# 94330_LM_IO_V1_2.net
KiCad netlist of a schematic drawn in Altium Designer
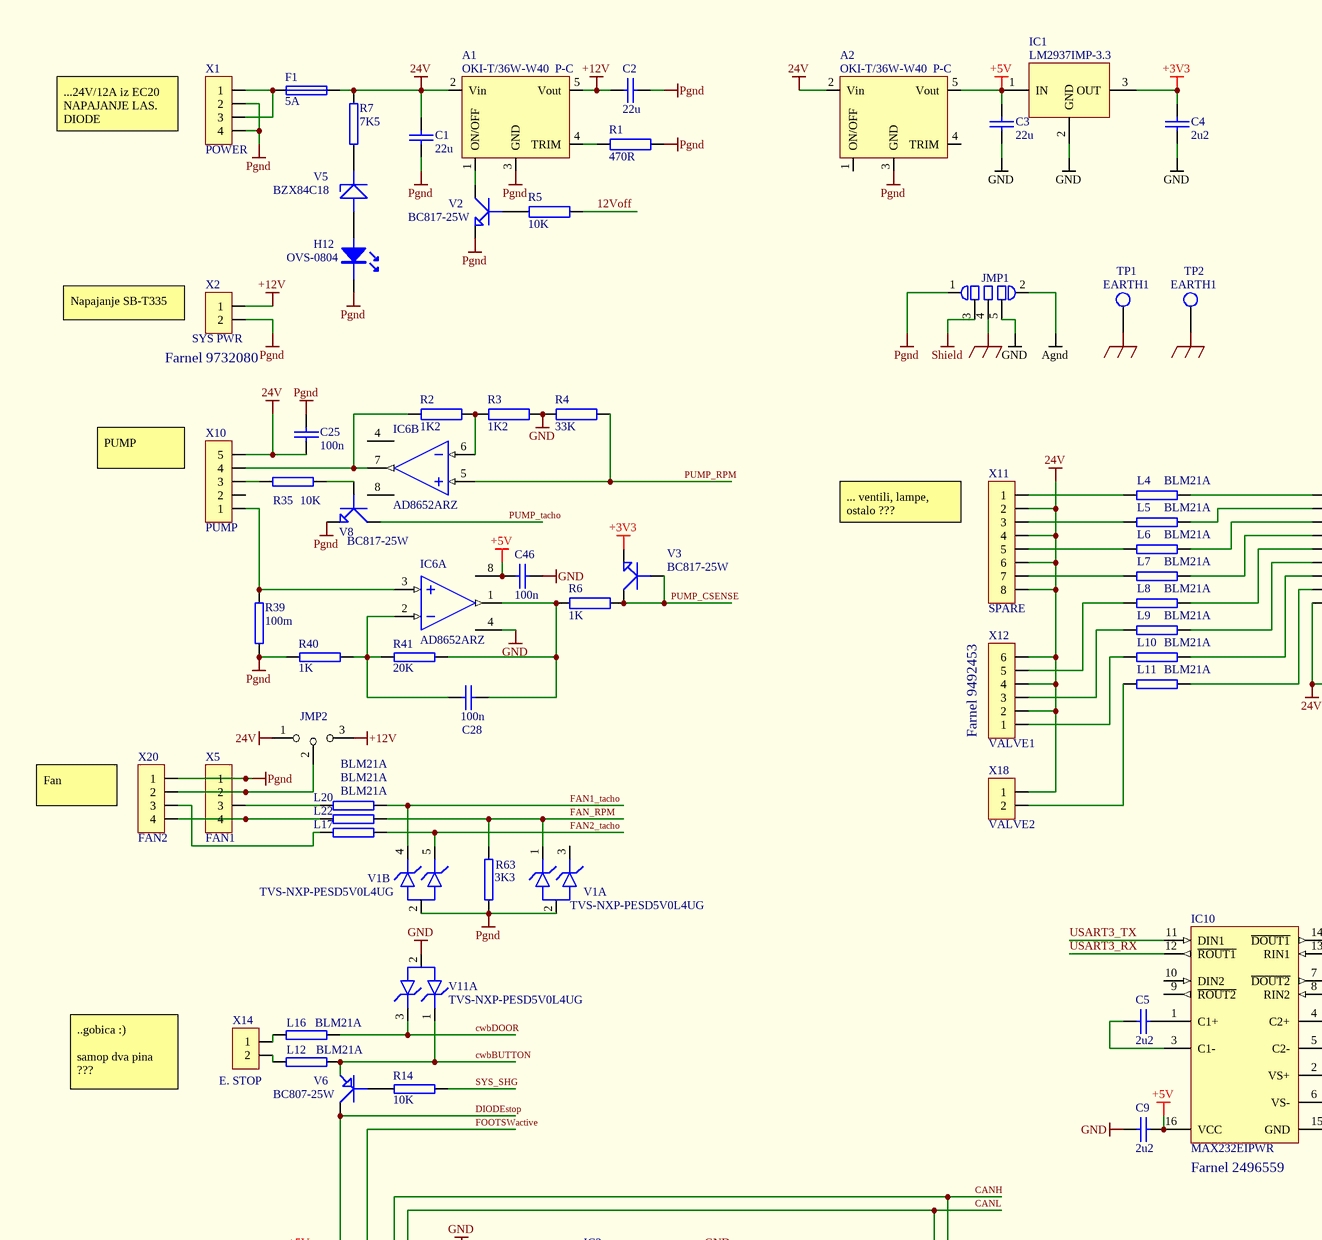
[diagram p0: 94330_LM_IO_V1.2.SchDoc, top left]
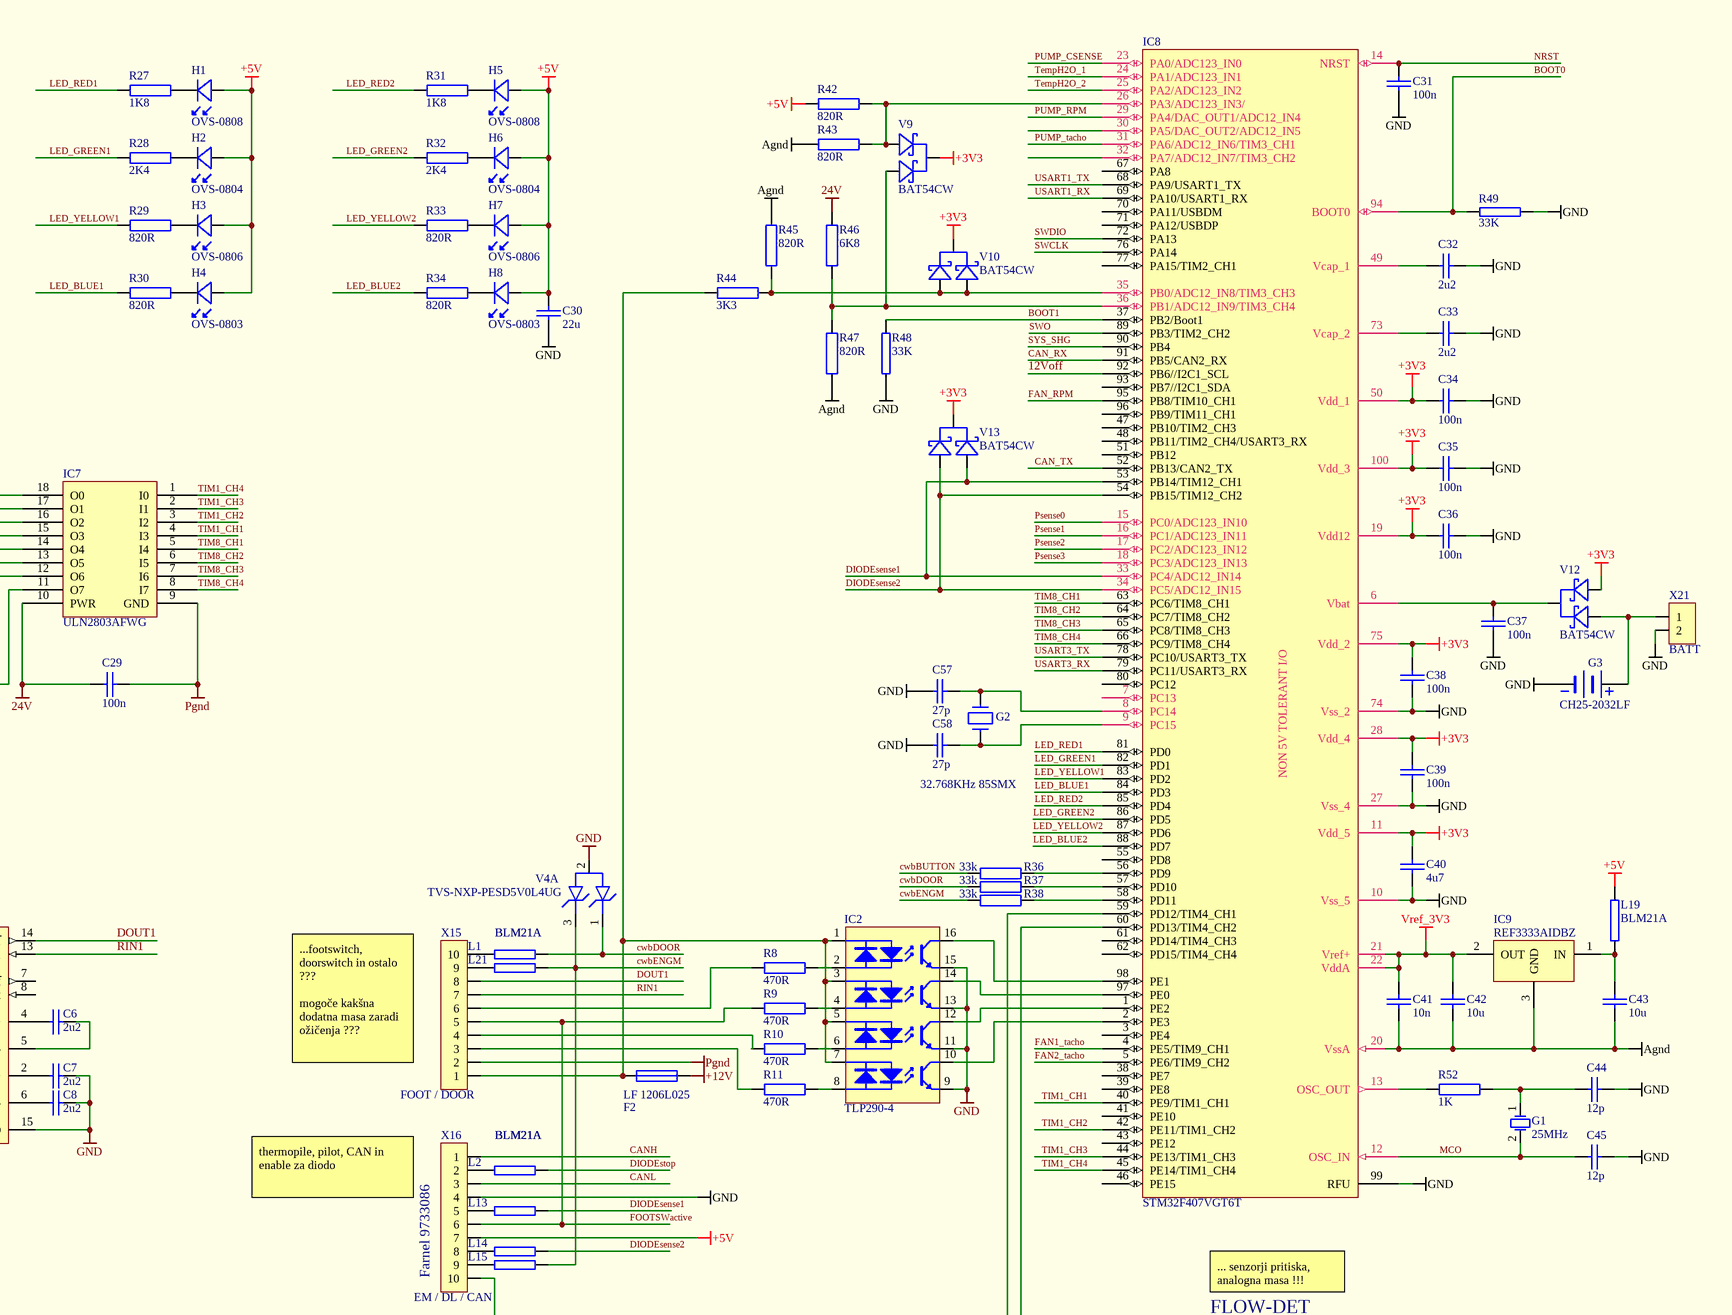
[diagram p1: 94330_LM_IO_V1.2.SchDoc, top right]
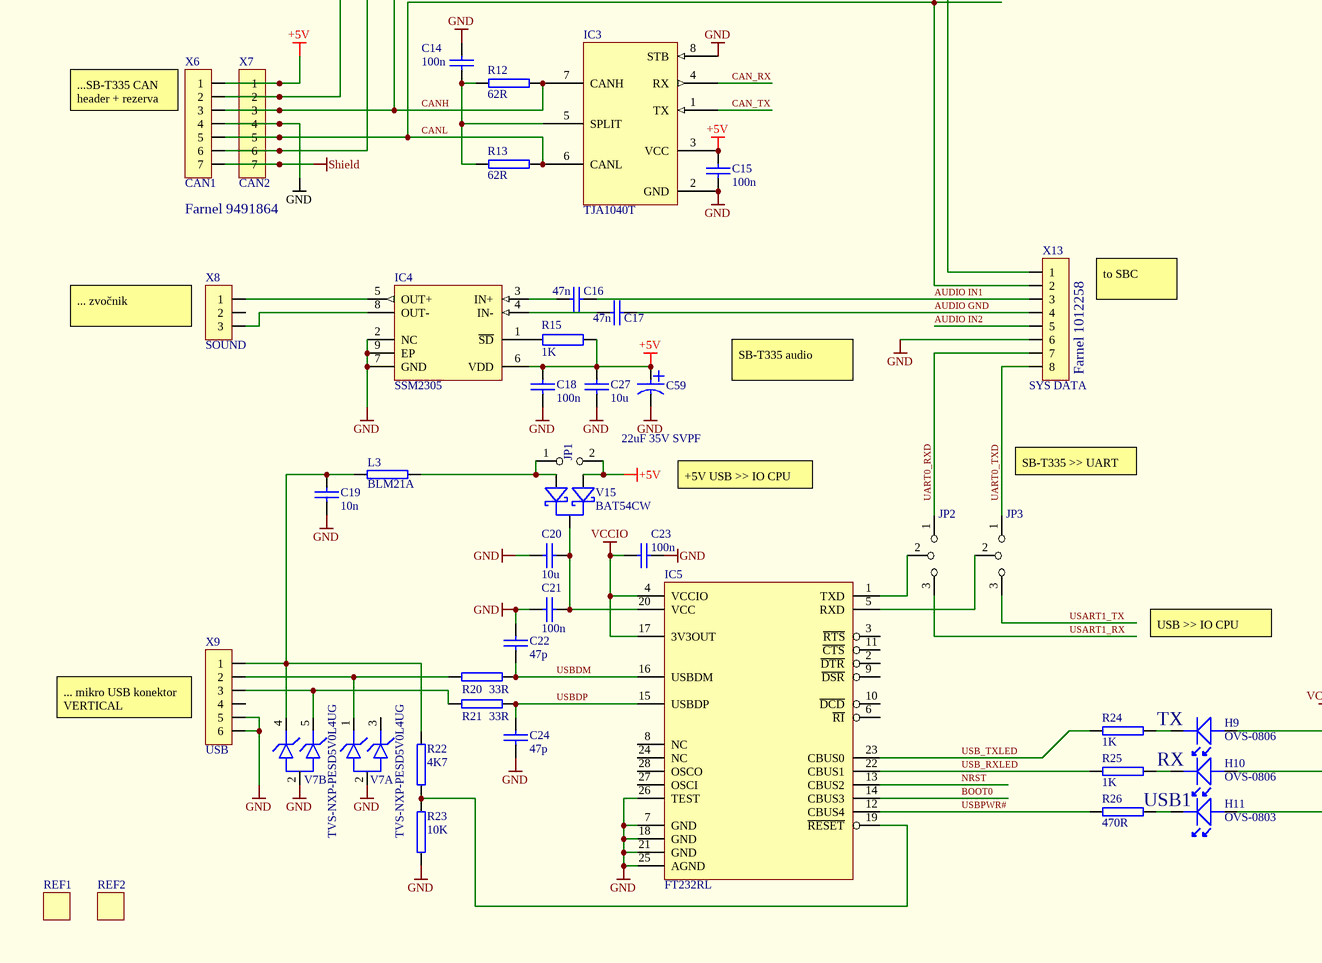
[diagram p2: 94330_LM_IO_V1.2.SchDoc, bottom left]
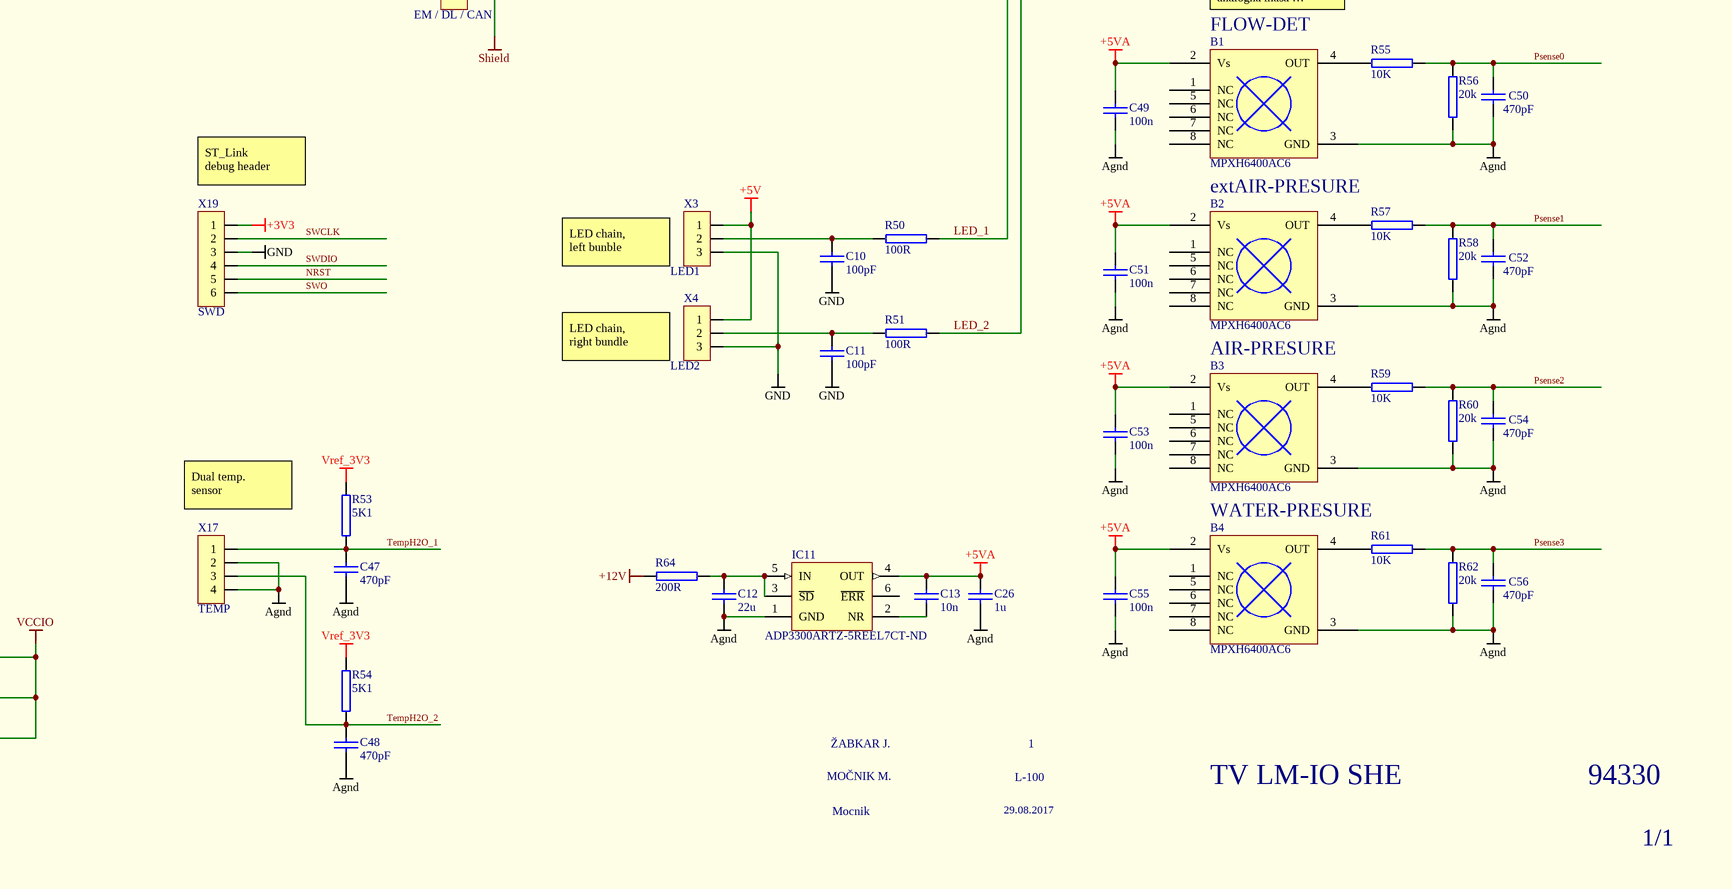
[diagram p3: 94330_LM_IO_V1.2.SchDoc, bottom right]

(export (version "E")
  (design (tool "Eeschema 10.0.6"))
  (components
    (comp (ref "A1")
      (value "OKI-T/36W-W40  P-C")
      (footprint "DC-DC_OKI-T/36W-W40")
      (libsource (lib "Mlk-sch") (part "MURATA_OKI-T/36W-W40  X-C"))
    )
    (comp (ref "A2")
      (value "OKI-T/36W-W40  P-C")
      (footprint "DC-DC_OKI-T/36W-W40")
      (libsource (lib "Mlk-sch") (part "MURATA_OKI-T/36W-W40  X-C"))
    )
    (comp (ref "B1")
      (value "MPXH6400AC6")
      (footprint "SOIC127P1030-8N_MPXH6400AC6")
      (description "MPXH6400A Pressure sensor, 400kPa")
      (libsource (lib "*") (part "MPXH6400A"))
    )
    (comp (ref "B2")
      (value "MPXH6400AC6")
      (footprint "SOIC127P1030-8N_MPXH6400AC6")
      (description "MPXH6400A Pressure sensor, 400kPa")
      (libsource (lib "*") (part "MPXH6400A"))
    )
    (comp (ref "B3")
      (value "MPXH6400AC6")
      (footprint "SOIC127P1030-8N_MPXH6400AC6")
      (description "MPXH6400A Pressure sensor, 400kPa")
      (libsource (lib "*") (part "MPXH6400A"))
    )
    (comp (ref "B4")
      (value "MPXH6400AC6")
      (footprint "SOIC127P1030-8N_MPXH6400AC6")
      (description "MPXH6400A Pressure sensor, 400kPa")
      (libsource (lib "*") (part "MPXH6400A"))
    )
    (comp (ref "C1")
      (value "22u")
      (footprint "CAPC3225N")
      (description "Capacitor 1206")
      (libsource (lib "altium-import") (part "root_2_Cap_"))
    )
    (comp (ref "C2")
      (value "22u")
      (footprint "CAPC3225N")
      (description "Capacitor 0805")
      (libsource (lib "altium-import") (part "root_1_Cap_"))
    )
    (comp (ref "C3")
      (value "22u")
      (footprint "CAPC3225N")
      (description "Capacitor 0805")
      (libsource (lib "altium-import") (part "root_0_Cap_"))
    )
    (comp (ref "C4")
      (value "2u2")
      (footprint "0805-C-IPC-V")
      (description "Capacitor 0805")
      (libsource (lib "altium-import") (part "root_0_Cap_"))
    )
    (comp (ref "C5")
      (value "2u2")
      (footprint "0805-C-IPC-V")
      (description "Capacitor 0805")
      (libsource (lib "altium-import") (part "root_1_Cap_"))
    )
    (comp (ref "C6")
      (value "2u2")
      (footprint "0805-C-IPC-V")
      (description "Capacitor 0805")
      (libsource (lib "altium-import") (part "root_1_Cap_"))
    )
    (comp (ref "C7")
      (value "2u2")
      (footprint "0805-C-IPC-V")
      (description "Capacitor 0805")
      (libsource (lib "altium-import") (part "root_1_Cap_"))
    )
    (comp (ref "C8")
      (value "2u2")
      (footprint "0805-C-IPC-V")
      (description "Capacitor 0805")
      (libsource (lib "altium-import") (part "root_1_Cap_"))
    )
    (comp (ref "C9")
      (value "2u2")
      (footprint "0805-C-IPC-V")
      (description "Capacitor 0805")
      (libsource (lib "altium-import") (part "root_3_Cap_"))
    )
    (comp (ref "C10")
      (value "100pF")
      (footprint "0805-C-IPC-V")
      (description "Capacitor 0805")
      (libsource (lib "*") (part "C"))
    )
    (comp (ref "C11")
      (value "100pF")
      (footprint "0805-C-IPC-V")
      (description "Capacitor 0805")
      (libsource (lib "*") (part "C"))
    )
    (comp (ref "C12")
      (value "22u")
      (footprint "CAPC3225N")
      (description "Capacitor 1206")
      (libsource (lib "altium-import") (part "root_2_Cap_"))
    )
    (comp (ref "C13")
      (value "10n")
      (footprint "0805-C-IPC-V")
      (description "Capacitor 0805")
      (libsource (lib "Main") (part "C"))
    )
    (comp (ref "C14")
      (value "100n")
      (footprint "0805-C-IPC-V")
      (description "Capacitor 0805")
      (libsource (lib "Main") (part "C"))
    )
    (comp (ref "C15")
      (value "100n")
      (footprint "0805-C-IPC-V")
      (description "Capacitor 0805")
      (libsource (lib "Main") (part "C"))
    )
    (comp (ref "C16")
      (value "47n")
      (footprint "0805-C-IPC-V")
      (description "Capacitor 0805")
      (libsource (lib "Main") (part "C"))
    )
    (comp (ref "C17")
      (value "47n")
      (footprint "0805-C-IPC-V")
      (description "Capacitor 0805")
      (libsource (lib "Main") (part "C"))
    )
    (comp (ref "C18")
      (value "100n")
      (footprint "0805-C-IPC-V")
      (description "Capacitor 0805")
      (libsource (lib "Main") (part "C"))
    )
    (comp (ref "C19")
      (value "10n")
      (footprint "0805-C-IPC-V")
      (description "Capacitor 0805")
      (libsource (lib "*") (part "C"))
    )
    (comp (ref "C20")
      (value "10u")
      (footprint "0805-C-IPC-V")
      (description "Capacitor 0805")
      (libsource (lib "*") (part "CAP"))
    )
    (comp (ref "C21")
      (value "100n")
      (footprint "0805-C-IPC-V")
      (description "Capacitor 0805")
      (libsource (lib "*") (part "C"))
    )
    (comp (ref "C22")
      (value "47p")
      (footprint "0805-C-V")
      (description "Capacitor 0805")
      (libsource (lib "*") (part "C"))
    )
    (comp (ref "C23")
      (value "100n")
      (footprint "0805-C-IPC-V")
      (description "Capacitor 0805")
      (libsource (lib "*") (part "C"))
    )
    (comp (ref "C24")
      (value "47p")
      (footprint "0805-C-V")
      (description "Capacitor 0805")
      (libsource (lib "*") (part "C"))
    )
    (comp (ref "C25")
      (value "100n")
      (footprint "0805-C-IPC-V")
      (description "Capacitor 0805")
      (libsource (lib "*") (part "C"))
    )
    (comp (ref "C26")
      (value "1u")
      (footprint "0805-C-IPC-V")
      (description "Capacitor 0805")
      (libsource (lib "Main") (part "C"))
    )
    (comp (ref "C27")
      (value "10u")
      (footprint "0805-C-IPC-V")
      (description "Capacitor 0805")
      (libsource (lib "altium-import") (part "root_2_Cap_"))
    )
    (comp (ref "C28")
      (value "100n")
      (footprint "0805-C-IPC-V")
      (description "Capacitor 0805")
      (libsource (lib "Fotona") (part "Cap"))
    )
    (comp (ref "C29")
      (value "100n")
      (footprint "0805-C-IPC-V")
      (description "Capacitor 0805")
      (libsource (lib "Main") (part "C"))
    )
    (comp (ref "C30")
      (value "22u")
      (footprint "0805-C-IPC-V")
      (description "Capacitor 0805")
      (libsource (lib "Fotona") (part "Cap"))
    )
    (comp (ref "C31")
      (value "100n")
      (footprint "0805-C-IPC-V")
      (description "Capacitor 0805")
      (libsource (lib "Fotona") (part "Cap"))
    )
    (comp (ref "C32")
      (value "2u2")
      (footprint "0805-C-IPC-V")
      (description "Capacitor 0805")
      (libsource (lib "Fotona") (part "Cap"))
    )
    (comp (ref "C33")
      (value "2u2")
      (footprint "0805-C-IPC-V")
      (description "Capacitor 0805")
      (libsource (lib "Fotona") (part "Cap"))
    )
    (comp (ref "C34")
      (value "100n")
      (footprint "0805-C-IPC-V")
      (description "Capacitor 0805")
      (libsource (lib "Main") (part "C"))
    )
    (comp (ref "C35")
      (value "100n")
      (footprint "0805-C-IPC-V")
      (description "Capacitor 0805")
      (libsource (lib "Main") (part "C"))
    )
    (comp (ref "C36")
      (value "100n")
      (footprint "0805-C-IPC-V")
      (description "Capacitor 0805")
      (libsource (lib "Main") (part "C"))
    )
    (comp (ref "C37")
      (value "100n")
      (footprint "0805-C-IPC-V")
      (description "Capacitor 0805")
      (libsource (lib "Main") (part "C"))
    )
    (comp (ref "C38")
      (value "100n")
      (footprint "0805-C-IPC-V")
      (description "Capacitor 0805")
      (libsource (lib "Main") (part "C"))
    )
    (comp (ref "C39")
      (value "100n")
      (footprint "0805-C-IPC-V")
      (description "Capacitor 0805")
      (libsource (lib "Main") (part "C"))
    )
    (comp (ref "C40")
      (value "4u7")
      (footprint "0805-C-IPC-V")
      (description "Capacitor 0805")
      (libsource (lib "Fotona") (part "Cap"))
    )
    (comp (ref "C41")
      (value "10n")
      (footprint "0805-C-IPC-V")
      (description "Capacitor 0805")
      (libsource (lib "Fotona") (part "Cap"))
    )
    (comp (ref "C42")
      (value "10u")
      (footprint "0805-C-IPC-V")
      (description "Capacitor 0805")
      (libsource (lib "Fotona") (part "Cap"))
    )
    (comp (ref "C43")
      (value "10u")
      (footprint "0805-C-IPC-V")
      (description "Capacitor 0805")
      (libsource (lib "Fotona") (part "Cap"))
    )
    (comp (ref "C44")
      (value "12p")
      (footprint "0805-C-IPC-V")
      (description "Capacitor 0603")
      (libsource (lib "Fotona") (part "Cap"))
    )
    (comp (ref "C45")
      (value "12p")
      (footprint "0805-C-IPC-V")
      (description "Capacitor 0603")
      (libsource (lib "Fotona") (part "Cap"))
    )
    (comp (ref "C46")
      (value "100n")
      (footprint "0805-C-IPC-V")
      (description "Capacitor 0805")
      (libsource (lib "Fotona") (part "Cap"))
    )
    (comp (ref "C47")
      (value "470pF")
      (footprint "0805-C-IPC-V")
      (description "Capacitor 0805")
      (libsource (lib "*") (part "C"))
    )
    (comp (ref "C48")
      (value "470pF")
      (footprint "0805-C-IPC-V")
      (description "Capacitor 0805")
      (libsource (lib "*") (part "C"))
    )
    (comp (ref "C49")
      (value "100n")
      (footprint "0805-C-IPC-V")
      (description "Capacitor 0805")
      (libsource (lib "Main") (part "C"))
    )
    (comp (ref "C50")
      (value "470pF")
      (footprint "0805-C-IPC-V")
      (description "Capacitor 0805")
      (libsource (lib "*") (part "C"))
    )
    (comp (ref "C51")
      (value "100n")
      (footprint "0805-C-IPC-V")
      (description "Capacitor 0805")
      (libsource (lib "Main") (part "C"))
    )
    (comp (ref "C52")
      (value "470pF")
      (footprint "0805-C-IPC-V")
      (description "Capacitor 0805")
      (libsource (lib "*") (part "C"))
    )
    (comp (ref "C53")
      (value "100n")
      (footprint "0805-C-IPC-V")
      (description "Capacitor 0805")
      (libsource (lib "Main") (part "C"))
    )
    (comp (ref "C54")
      (value "470pF")
      (footprint "0805-C-IPC-V")
      (description "Capacitor 0805")
      (libsource (lib "*") (part "C"))
    )
    (comp (ref "C55")
      (value "100n")
      (footprint "0805-C-IPC-V")
      (description "Capacitor 0805")
      (libsource (lib "Main") (part "C"))
    )
    (comp (ref "C56")
      (value "470pF")
      (footprint "0805-C-IPC-V")
      (description "Capacitor 0805")
      (libsource (lib "*") (part "C"))
    )
    (comp (ref "C57")
      (value "27p")
      (footprint "0805-C-IPC-V")
      (description "Capacitor 0603")
      (libsource (lib "Fotona") (part "Cap"))
    )
    (comp (ref "C58")
      (value "27p")
      (footprint "0805-C-IPC-V")
      (description "Capacitor 0603")
      (libsource (lib "Fotona") (part "Cap"))
    )
    (comp (ref "C59")
      (value "22uF 35V SVPF")
      (footprint "CAPAE66W54HN")
      (libsource (lib "Mlk-sch") (part "C-EL"))
    )
    (comp (ref "F1")
      (value "5A")
      (footprint "FUSE_154_ LITTELFUSE")
      (description "FUSE")
      (libsource (lib "MA_DEVICE_1") (part "FUSE"))
    )
    (comp (ref "F2") (value "LF 1206L025") (footprint "FUSEC3216X09N") (libsource (lib "*") (part "FUSE1")))
    (comp (ref "G1")
      (value "25MHz")
      (footprint "JXG53P2")
      (description "SMD Quartz Crystal")
      (libsource (lib "Fotona") (part "XTAL"))
    )
    (comp (ref "G2")
      (value "32.768KHz 85SMX")
      (footprint "QUARTZ-85SMX")
      (libsource (lib "*") (part "CRYSTAL"))
    )
    (comp (ref "G3")
      (value "CH25-2032LF")
      (footprint "BATTERY HOLDER-20")
      (description "Li CELL 3V, 3/2 PIN, HOR/VERT POS")
      (libsource (lib "Mlk-sch") (part "BATTERY LI 3V"))
    )
    (comp (ref "H1")
      (value "OVS-0808")
      (footprint "LED_0805_RED")
      (description "LED")
      (libsource (lib "Fotona") (part "LED"))
    )
    (comp (ref "H2")
      (value "OVS-0804")
      (footprint "LED_0805_GREEN")
      (description "LED")
      (libsource (lib "Fotona") (part "LED"))
    )
    (comp (ref "H3")
      (value "OVS-0806")
      (footprint "LED_0805_YELLOW")
      (description "LED")
      (libsource (lib "Fotona") (part "LED"))
    )
    (comp (ref "H4")
      (value "OVS-0803")
      (footprint "LED_0805_BLUE")
      (description "LED")
      (libsource (lib "Fotona") (part "LED"))
    )
    (comp (ref "H5")
      (value "OVS-0808")
      (footprint "LED_0805_RED")
      (description "LED")
      (libsource (lib "Fotona") (part "LED"))
    )
    (comp (ref "H6")
      (value "OVS-0804")
      (footprint "LED_0805_GREEN")
      (description "LED")
      (libsource (lib "Fotona") (part "LED"))
    )
    (comp (ref "H7")
      (value "OVS-0806")
      (footprint "LED_0805_YELLOW")
      (description "LED")
      (libsource (lib "Fotona") (part "LED"))
    )
    (comp (ref "H8")
      (value "OVS-0803")
      (footprint "LED_0805_BLUE")
      (description "LED")
      (libsource (lib "Fotona") (part "LED"))
    )
    (comp (ref "H9")
      (value "OVS-0806")
      (footprint "LED_0805_YELLOW")
      (description "LED")
      (libsource (lib "*") (part "LED0805"))
    )
    (comp (ref "H10")
      (value "OVS-0806")
      (footprint "LED_0805_YELLOW")
      (description "LED")
      (libsource (lib "*") (part "LED0805"))
    )
    (comp (ref "H11")
      (value "OVS-0803")
      (footprint "LED_0805_BLUE")
      (description "LED")
      (libsource (lib "*") (part "LED0805"))
    )
    (comp (ref "H12")
      (value "OVS-0804")
      (footprint "LED_0805_GREEN")
      (description "LED")
      (libsource (lib "MA_DEVICE_1") (part "D_LED"))
    )
    (comp (ref "IC1")
      (value "LM2937IMP-3.3")
      (footprint "FOTONA_IPC7351_DISCRETE:SOT223-4N-V")
      (description "Fixed 3V3 Regulator")
      (libsource (lib "Fotona") (part "LM2937IMP"))
    )
    (comp (ref "IC2")
      (value "TLP290-4")
      (footprint "SOIC127P700X265-16N")
      (libsource (lib "Mlk-sch") (part "OPTOCOUPLER-QUAD"))
    )
    (comp (ref "IC3") (value "TJA1040T") (footprint "SO_8") (libsource (lib "*") (part "TJA1040")))
    (comp (ref "IC4")
      (value "SSM2305")
      (footprint "SON50P300X85_HS-9N")
      (libsource (lib "Mlk-sch") (part "SSM2305"))
    )
    (comp (ref "IC5")
      (value "FT232RL")
      (footprint "SOP65P780-28N")
      (description "USB to Serial port converter")
      (libsource (lib "*") (part "FT232RL"))
    )
    (comp (ref "IC6")
      (value "AD8652ARZ")
      (footprint "SOIC127P600-8N")
      (description "Dual CMOS RR Op Amp")
      (libsource (lib "Fotona") (part "OPAMP_DUAL"))
    )
    (comp (ref "IC7")
      (value "ULN2803AFWG")
      (footprint "SOIC127P1030-18N")
      (description "COIL DRIVER")
      (libsource (lib "*") (part "ULN2804"))
    )
    (comp (ref "IC8")
      (value "STM32F407VGT6T")
      (footprint "LQFP100_N")
      (description "STM32 ARM-based 32-bit MCU with 1024 Kbytes Flash, 100-pin LQFP")
      (libsource (lib "Fotona") (part "STM32F205VGT6"))
    )
    (comp (ref "IC9")
      (value "REF3333AIDBZ")
      (footprint "FOTONA_IPC7351_DISCRETE:SOT23-3N")
      (description "3V3 Voltage Reference")
      (libsource (lib "Fotona") (part "REF33XX"))
    )
    (comp (ref "IC10")
      (value "MAX232EIPWR")
      (footprint "FOTONA_IPC7351_SO:TSOP65P640-16N")
      (libsource (lib "altium-import") (part "root_0_CMP-0299-00572-2_"))
    )
    (comp (ref "IC11")
      (value "ADP3300ARTZ-5REEL7CT-ND")
      (footprint "SOT23-6N")
      (libsource (lib "Mlk-sch") (part "ADP3300"))
    )
    (comp (ref "JMP1") (value "~") (libsource (lib "*") (part "JUMPER SMD5X")))
    (comp (ref "JMP2") (value "~") (description "JUMPER") (libsource (lib "MA_DEVICE_1") (part "JMP3")))
    (comp (ref "JP1")
      (value "JMP2")
      (footprint "SIP_2")
      (description "JUMPER")
      (libsource (lib "MA_DEVICE_1") (part "JMP2"))
    )
    (comp (ref "JP2")
      (value "~")
      (footprint "SIP_3")
      (description "JUMPER")
      (libsource (lib "MA_DEVICE_1") (part "JMP3"))
    )
    (comp (ref "JP3")
      (value "~")
      (footprint "SIP_3")
      (description "JUMPER")
      (libsource (lib "MA_DEVICE_1") (part "JMP3"))
    )
    (comp (ref "L1")
      (value "BLM21A")
      (footprint "INDC2012N")
      (description "Ferite Bead SMT")
      (libsource (lib "*") (part "BLM21"))
    )
    (comp (ref "L2")
      (value "BLM21A")
      (footprint "INDC2012N")
      (description "Ferite Bead SMT")
      (libsource (lib "*") (part "BLM21"))
    )
    (comp (ref "L3")
      (value "BLM21A")
      (footprint "INDC2012N")
      (description "Ferite Bead SMT")
      (libsource (lib "*") (part "BLM21"))
    )
    (comp (ref "L4")
      (value "BLM21A")
      (footprint "INDC2012N")
      (description "FERITE MURATA BLM21")
      (libsource (lib "*") (part "BLM21"))
    )
    (comp (ref "L5")
      (value "BLM21A")
      (footprint "INDC2012N")
      (description "FERITE MURATA BLM21")
      (libsource (lib "*") (part "BLM21"))
    )
    (comp (ref "L6")
      (value "BLM21A")
      (footprint "INDC2012N")
      (description "FERITE MURATA BLM21")
      (libsource (lib "*") (part "BLM21"))
    )
    (comp (ref "L7")
      (value "BLM21A")
      (footprint "INDC2012N")
      (description "FERITE MURATA BLM21")
      (libsource (lib "*") (part "BLM21"))
    )
    (comp (ref "L8")
      (value "BLM21A")
      (footprint "INDC2012N")
      (description "FERITE MURATA BLM21")
      (libsource (lib "*") (part "BLM21"))
    )
    (comp (ref "L9")
      (value "BLM21A")
      (footprint "INDC2012N")
      (description "FERITE MURATA BLM21")
      (libsource (lib "*") (part "BLM21"))
    )
    (comp (ref "L10")
      (value "BLM21A")
      (footprint "INDC2012N")
      (description "FERITE MURATA BLM21")
      (libsource (lib "*") (part "BLM21"))
    )
    (comp (ref "L11")
      (value "BLM21A")
      (footprint "INDC2012N")
      (description "FERITE MURATA BLM21")
      (libsource (lib "*") (part "BLM21"))
    )
    (comp (ref "L12")
      (value "BLM21A")
      (footprint "INDC2012N")
      (description "Ferite Bead SMT")
      (libsource (lib "*") (part "BLM21"))
    )
    (comp (ref "L13")
      (value "BLM21A")
      (footprint "INDC2012N")
      (description "Ferite Bead SMT")
      (libsource (lib "*") (part "BLM21"))
    )
    (comp (ref "L14")
      (value "BLM21A")
      (footprint "INDC2012N")
      (description "Ferite Bead SMT")
      (libsource (lib "*") (part "BLM21"))
    )
    (comp (ref "L15")
      (value "BLM21A")
      (footprint "INDC2012N")
      (description "Ferite Bead SMT")
      (libsource (lib "*") (part "BLM21"))
    )
    (comp (ref "L16")
      (value "BLM21A")
      (footprint "INDC2012N")
      (description "Ferite Bead SMT")
      (libsource (lib "*") (part "BLM21"))
    )
    (comp (ref "L17")
      (value "BLM21A")
      (footprint "INDC2012N")
      (description "FERITE MURATA BLM21")
      (libsource (lib "*") (part "BLM21"))
    )
    (comp (ref "L19")
      (value "BLM21A")
      (footprint "INDC2012N")
      (description "Ferite Bead SMT")
      (libsource (lib "*") (part "BLM21"))
    )
    (comp (ref "L20")
      (value "BLM21A")
      (footprint "INDC2012N")
      (description "FERITE MURATA BLM21")
      (libsource (lib "*") (part "BLM21"))
    )
    (comp (ref "L21")
      (value "BLM21A")
      (footprint "INDC2012N")
      (description "Ferite Bead SMT")
      (libsource (lib "*") (part "BLM21"))
    )
    (comp (ref "L22")
      (value "BLM21A")
      (footprint "INDC2012N")
      (description "FERITE MURATA BLM21")
      (libsource (lib "*") (part "BLM21"))
    )
    (comp (ref "R1")
      (value "470R")
      (footprint "0805-R-IPC-V")
      (description "Chip Resistor 0805")
      (libsource (lib "Fotona") (part "Res"))
    )
    (comp (ref "R2")
      (value "1K2")
      (footprint "0805-R-IPC-V")
      (description "Chip Resistor 0805")
      (libsource (lib "Fotona") (part "Res"))
    )
    (comp (ref "R3")
      (value "1K2")
      (footprint "0805-R-IPC-V")
      (description "Chip Resistor 0805")
      (libsource (lib "Fotona") (part "Res"))
    )
    (comp (ref "R4")
      (value "33K")
      (footprint "0805-R-V")
      (description "Chip Resistor 0805")
      (libsource (lib "Fotona") (part "Res"))
    )
    (comp (ref "R5")
      (value "10K")
      (footprint "0805-R-IPC-V")
      (description "Chip Resistor 0805")
      (libsource (lib "Fotona") (part "Res"))
    )
    (comp (ref "R6")
      (value "1K")
      (footprint "0805-R-IPC-V")
      (description "Chip Resistor 0805")
      (libsource (lib "Fotona") (part "Res"))
    )
    (comp (ref "R7")
      (value "7K5")
      (footprint "0805-R-IPC-V")
      (description "Resistor")
      (libsource (lib "*") (part "R"))
    )
    (comp (ref "R8")
      (value "470R")
      (footprint "0805-R-IPC-V")
      (description "Chip Resistor 0805")
      (libsource (lib "Fotona") (part "Res"))
    )
    (comp (ref "R9")
      (value "470R")
      (footprint "0805-R-IPC-V")
      (description "Chip Resistor 0805")
      (libsource (lib "Fotona") (part "Res"))
    )
    (comp (ref "R10")
      (value "470R")
      (footprint "0805-R-IPC-V")
      (description "Chip Resistor 0805")
      (libsource (lib "Fotona") (part "Res"))
    )
    (comp (ref "R11")
      (value "470R")
      (footprint "0805-R-IPC-V")
      (description "Chip Resistor 0805")
      (libsource (lib "Fotona") (part "Res"))
    )
    (comp (ref "R12")
      (value "62R")
      (footprint "0805-R-IPC-V")
      (description "Resistor")
      (libsource (lib "Main") (part "R"))
    )
    (comp (ref "R13")
      (value "62R")
      (footprint "0805-R-IPC-V")
      (description "Resistor")
      (libsource (lib "Main") (part "R"))
    )
    (comp (ref "R14")
      (value "10K")
      (footprint "0805-R-IPC-V")
      (description "Resistor")
      (libsource (lib "Main") (part "R"))
    )
    (comp (ref "R15")
      (value "1K")
      (footprint "0805-R-IPC-V")
      (description "Chip Resistor 0805")
      (libsource (lib "Fotona") (part "Res"))
    )
    (comp (ref "R20")
      (value "33R")
      (footprint "0805-R-IPC-V")
      (description "Resistor")
      (libsource (lib "*") (part "R"))
    )
    (comp (ref "R21")
      (value "33R")
      (footprint "0805-R-IPC-V")
      (description "Resistor")
      (libsource (lib "*") (part "R"))
    )
    (comp (ref "R22")
      (value "4K7")
      (footprint "0805-R-IPC-V")
      (description "Resistor")
      (libsource (lib "*") (part "R"))
    )
    (comp (ref "R23")
      (value "10K")
      (footprint "0805-R-IPC-V")
      (description "Resistor")
      (libsource (lib "*") (part "R"))
    )
    (comp (ref "R24")
      (value "1K")
      (footprint "0805-R-IPC-V")
      (description "Resistor")
      (libsource (lib "*") (part "R"))
    )
    (comp (ref "R25")
      (value "1K")
      (footprint "0805-R-IPC-V")
      (description "Resistor")
      (libsource (lib "*") (part "R"))
    )
    (comp (ref "R26")
      (value "470R")
      (footprint "0805-R-IPC-V")
      (description "Resistor")
      (libsource (lib "*") (part "R"))
    )
    (comp (ref "R27")
      (value "1K8")
      (footprint "0805-R-IPC-V")
      (description "Chip Resistor 0805")
      (libsource (lib "Fotona") (part "Res"))
    )
    (comp (ref "R28")
      (value "2K4")
      (footprint "0805-R-IPC-V")
      (description "Chip Resistor 0805")
      (libsource (lib "Fotona") (part "Res"))
    )
    (comp (ref "R29")
      (value "820R")
      (footprint "0805-R-IPC-V")
      (description "Chip Resistor 0805")
      (libsource (lib "Fotona") (part "Res"))
    )
    (comp (ref "R30")
      (value "820R")
      (footprint "0805-R-IPC-V")
      (description "Chip Resistor 0805")
      (libsource (lib "Fotona") (part "Res"))
    )
    (comp (ref "R31")
      (value "1K8")
      (footprint "0805-R-IPC-V")
      (description "Chip Resistor 0805")
      (libsource (lib "Fotona") (part "Res"))
    )
    (comp (ref "R32")
      (value "2K4")
      (footprint "0805-R-IPC-V")
      (description "Chip Resistor 0805")
      (libsource (lib "Fotona") (part "Res"))
    )
    (comp (ref "R33")
      (value "820R")
      (footprint "0805-R-IPC-V")
      (description "Chip Resistor 0805")
      (libsource (lib "Fotona") (part "Res"))
    )
    (comp (ref "R34")
      (value "820R")
      (footprint "0805-R-IPC-V")
      (description "Chip Resistor 0805")
      (libsource (lib "Fotona") (part "Res"))
    )
    (comp (ref "R35")
      (value "10K")
      (footprint "0805-R-IPC-V")
      (description "Resistor")
      (libsource (lib "Main") (part "R"))
    )
    (comp (ref "R36")
      (value "33k")
      (footprint "0805-R-IPC-V")
      (description "Chip Resistor 0402")
      (fields (field (name "TOLERANCE") "1%") (field (name "POWER") "0.063W"))
      (libsource (lib "Fotona") (part "Res"))
    )
    (comp (ref "R37")
      (value "33k")
      (footprint "0805-R-IPC-V")
      (description "Chip Resistor 0402")
      (fields (field (name "TOLERANCE") "1%") (field (name "POWER") "0.063W"))
      (libsource (lib "Fotona") (part "Res"))
    )
    (comp (ref "R38")
      (value "33k")
      (footprint "0805-R-IPC-V")
      (description "Chip Resistor 0402")
      (fields (field (name "TOLERANCE") "1%") (field (name "POWER") "0.063W"))
      (libsource (lib "Fotona") (part "Res"))
    )
    (comp (ref "R39")
      (value "100m")
      (footprint "RESC3216N")
      (description "Resistor")
      (libsource (lib "Main") (part "R"))
    )
    (comp (ref "R40")
      (value "1K")
      (footprint "0805-R-IPC-V")
      (description "Resistor")
      (libsource (lib "Main") (part "R"))
    )
    (comp (ref "R41")
      (value "20K")
      (footprint "0805-R-IPC-V")
      (description "Resistor")
      (libsource (lib "Main") (part "R"))
    )
    (comp (ref "R42")
      (value "820R")
      (footprint "0805-R-IPC-V")
      (description "Chip Resistor 0805")
      (libsource (lib "Fotona") (part "Res"))
    )
    (comp (ref "R43")
      (value "820R")
      (footprint "0805-R-IPC-V")
      (description "Chip Resistor 0805")
      (libsource (lib "Fotona") (part "Res"))
    )
    (comp (ref "R44")
      (value "3K3")
      (footprint "0805-R-IPC-V")
      (description "Chip Resistor 0805")
      (libsource (lib "Fotona") (part "Res"))
    )
    (comp (ref "R45")
      (value "820R")
      (footprint "0805-R-IPC-V")
      (description "Chip Resistor 0805")
      (libsource (lib "Fotona") (part "Res"))
    )
    (comp (ref "R46")
      (value "6K8")
      (footprint "0805-R-IPC-V")
      (description "Chip Resistor 0805")
      (libsource (lib "Fotona") (part "Res"))
    )
    (comp (ref "R47")
      (value "820R")
      (footprint "0805-R-IPC-V")
      (description "Chip Resistor 0805")
      (libsource (lib "Fotona") (part "Res"))
    )
    (comp (ref "R48")
      (value "33K")
      (footprint "0805-R-IPC-V")
      (description "Resistor")
      (libsource (lib "Main") (part "R"))
    )
    (comp (ref "R49")
      (value "33K")
      (footprint "0805-R-IPC-V")
      (description "Resistor")
      (libsource (lib "Main") (part "R"))
    )
    (comp (ref "R50")
      (value "100R")
      (footprint "0805-R-IPC-V")
      (description "Resistor")
      (libsource (lib "Main") (part "R"))
    )
    (comp (ref "R51")
      (value "100R")
      (footprint "0805-R-IPC-V")
      (description "Resistor")
      (libsource (lib "Main") (part "R"))
    )
    (comp (ref "R52")
      (value "1K")
      (footprint "0805-R-IPC-V")
      (description "Resistor")
      (libsource (lib "Fotona") (part "Res"))
    )
    (comp (ref "R53")
      (value "5K1")
      (footprint "0805-R-IPC-V")
      (description "Resistor")
      (libsource (lib "Main") (part "R"))
    )
    (comp (ref "R54")
      (value "5K1")
      (footprint "0805-R-IPC-V")
      (description "Resistor")
      (libsource (lib "Main") (part "R"))
    )
    (comp (ref "R55")
      (value "10K")
      (footprint "0805-R-IPC-V")
      (description "Resistor")
      (libsource (lib "Main") (part "R"))
    )
    (comp (ref "R56")
      (value "20k")
      (footprint "0805-R-IPC-V")
      (description "Resistor 0805")
      (libsource (lib "Main") (part "R"))
    )
    (comp (ref "R57")
      (value "10K")
      (footprint "0805-R-IPC-V")
      (description "Resistor")
      (libsource (lib "Main") (part "R"))
    )
    (comp (ref "R58")
      (value "20k")
      (footprint "0805-R-IPC-V")
      (description "Resistor 0805")
      (libsource (lib "Main") (part "R"))
    )
    (comp (ref "R59")
      (value "10K")
      (footprint "0805-R-IPC-V")
      (description "Resistor")
      (libsource (lib "Main") (part "R"))
    )
    (comp (ref "R60")
      (value "20k")
      (footprint "0805-R-IPC-V")
      (description "Resistor 0805")
      (libsource (lib "Main") (part "R"))
    )
    (comp (ref "R61")
      (value "10K")
      (footprint "0805-R-IPC-V")
      (description "Resistor")
      (libsource (lib "Main") (part "R"))
    )
    (comp (ref "R62")
      (value "20k")
      (footprint "0805-R-IPC-V")
      (description "Resistor 0805")
      (libsource (lib "Main") (part "R"))
    )
    (comp (ref "R63")
      (value "3K3")
      (footprint "0805-R-IPC-V")
      (description "Resistor")
      (libsource (lib "Main") (part "R"))
    )
    (comp (ref "R64")
      (value "200R")
      (footprint "RESC3216N")
      (description "Resistor")
      (libsource (lib "Main") (part "R"))
    )
    (comp (ref "REF1")
      (value "MEHAN_PART_1")
      (footprint "TP_REF")
      (libsource (lib "Altium_Device_AM_1") (part "MEHAN_PART_1"))
    )
    (comp (ref "REF2")
      (value "~")
      (footprint "TP_REF")
      (libsource (lib "Altium_Device_AM_1") (part "MEHAN_PART_1"))
    )
    (comp (ref "TP1") (value "EARTH1") (footprint "PAD") (libsource (lib "*") (part "TP")))
    (comp (ref "TP2") (value "EARTH1") (footprint "PAD") (libsource (lib "*") (part "TP")))
    (comp (ref "V1")
      (value "TVS-NXP-PESD5V0L4UG")
      (footprint "SC70-5")
      (description "TVS, NXP, PESD3V3L4UG, SOT665")
      (libsource (lib "*") (part "TVS-NXP-PESD3V3L4UG"))
    )
    (comp (ref "V2")
      (value "BC817-25W")
      (footprint "SOT323-3N-CBE")
      (description "NPN Bipolar Transistor")
      (libsource (lib "Fotona") (part "TRANSISTOR_NPN"))
    )
    (comp (ref "V3")
      (value "BC817-25W")
      (footprint "SOT323-3N-CBE")
      (description "NPN Bipolar Transistor")
      (libsource (lib "Fotona") (part "TRANSISTOR_NPN_1B_2E_3C"))
    )
    (comp (ref "V4")
      (value "TVS-NXP-PESD5V0L4UG")
      (footprint "SC70-5")
      (description "TVS, NXP, PESD3V3L4UG, SOT665")
      (libsource (lib "*") (part "TVS-NXP-PESD3V3L4UG"))
    )
    (comp (ref "V5")
      (value "BZX84C18")
      (footprint "SOT_23/D1")
      (description "Zener Diode")
      (libsource (lib "*") (part "ZD"))
    )
    (comp (ref "V6")
      (value "BC807-25W")
      (footprint "SOT323-3N-CBE")
      (description "PNP Bipolar Transistor")
      (libsource (lib "Fotona") (part "TRANSISTOR_PNP_1B_2E_3C"))
    )
    (comp (ref "V7")
      (value "TVS-NXP-PESD5V0L4UG")
      (footprint "SC70-5")
      (description "TVS, NXP, PESD3V3L4UG, SOT665")
      (libsource (lib "*") (part "TVS-NXP-PESD3V3L4UG"))
    )
    (comp (ref "V8")
      (value "BC817-25W")
      (footprint "SOT323-3N-CBE")
      (description "NPN Bipolar Transistor")
      (libsource (lib "Fotona") (part "TRANSISTOR_NPN"))
    )
    (comp (ref "V9")
      (value "BAT54CW")
      (footprint "FOTONA_IPC7351_DISCRETE:SOT323-3N")
      (description "Diode Schottky Common Chatode")
      (libsource (lib "Fotona") (part "D_SCH_CK_1A1-2A2-3K"))
    )
    (comp (ref "V10")
      (value "BAT54CW")
      (footprint "FOTONA_IPC7351_DISCRETE:SOT323-3N")
      (description "Diode Schottky Common Chatode")
      (libsource (lib "Fotona") (part "D_SCH_CK_1A1-2A2-3K"))
    )
    (comp (ref "V11")
      (value "TVS-NXP-PESD5V0L4UG")
      (footprint "SC70-5")
      (description "TVS, NXP, PESD3V3L4UG, SOT665")
      (libsource (lib "*") (part "TVS-NXP-PESD3V3L4UG"))
    )
    (comp (ref "V12")
      (value "BAT54CW")
      (footprint "FOTONA_IPC7351_DISCRETE:SOT323-3N")
      (description "Diode Schottky Common Chatode")
      (libsource (lib "Fotona") (part "D_SCH_CK_1A1-2A2-3K"))
    )
    (comp (ref "V13")
      (value "BAT54CW")
      (footprint "FOTONA_IPC7351_DISCRETE:SOT323-3N")
      (description "Diode Schottky Common Chatode")
      (libsource (lib "Fotona") (part "D_SCH_CK_1A1-2A2-3K"))
    )
    (comp (ref "V15")
      (value "BAT54CW")
      (footprint "FOTONA_IPC7351_DISCRETE:SOT323-3N")
      (description "Diode Schottky Common Chatode")
      (libsource (lib "Fotona") (part "D_SCH_CK_1A1-2A2-3K"))
    )
    (comp (ref "X1")
      (value "POWER")
      (footprint "CON_4.2_4X_V")
      (description "CONNECTOR")
      (libsource (lib "MA_CONNECT_1") (part "CON 4"))
    )
    (comp (ref "X2")
      (value "SYS PWR")
      (footprint "CON_3.0_2X_V_DUAL ROW")
      (description "Male 2mm Vertical Header 2 Pin")
      (libsource (lib "") (part "CON2_1"))
    )
    (comp (ref "X3") (value "LED1") (footprint "CON-PH_3PIN_JST") (libsource (lib "Device") (part "CON3")))
    (comp (ref "X4") (value "LED2") (footprint "CON-PH_3PIN_JST") (libsource (lib "Device") (part "CON3")))
    (comp (ref "X5")
      (value "FAN1")
      (footprint "MOLEX_47053-1000")
      (description "CONNECTOR")
      (libsource (lib "MA_CONNECT_1") (part "CON 4"))
    )
    (comp (ref "X6") (value "CAN1") (footprint "CON-PH_7PIN_JST") (libsource (lib "Mlk-sch") (part "CON7")))
    (comp (ref "X7") (value "CAN2") (footprint "CON-PH_7PIN_JST") (libsource (lib "Mlk-sch") (part "CON7")))
    (comp (ref "X8")
      (value "SOUND")
      (footprint "CON-MOLEX-53047-0310")
      (libsource (lib "Device") (part "CON3"))
    )
    (comp (ref "X9")
      (value "USB")
      (footprint "CON_uUSB_TOP")
      (description "USB B Micro  Female SMD Horizontal")
      (libsource (lib "Fotona") (part "CON6"))
    )
    (comp (ref "X10")
      (value "PUMP")
      (footprint "CON-PH_5PIN_JST")
      (description "CONNECTOR")
      (libsource (lib "MA_CONNECT_1") (part "CON 5"))
    )
    (comp (ref "X11")
      (value "SPARE")
      (footprint "CON-PH_8PIN_JST")
      (description "CONNECTOR")
      (libsource (lib "") (part "CON 8_1"))
    )
    (comp (ref "X12")
      (value "VALVE1")
      (footprint "CON-PH_6PIN_JST")
      (description "CONNECTOR")
      (libsource (lib "MA_CONNECT_1") (part "CON 6"))
    )
    (comp (ref "X13")
      (value "SYS DATA")
      (footprint "CON-MOLEX-53047-0810")
      (description "CONNECTOR")
      (libsource (lib "MA_CONNECT_1") (part "CON 8"))
    )
    (comp (ref "X14")
      (value "E. STOP")
      (footprint "CON-PH_2PIN_JST")
      (description "Right Angle Header SMD 2 pin")
      (libsource (lib "") (part "CON2_1"))
    )
    (comp (ref "X15")
      (value "FOOT / DOOR")
      (footprint "CON-PH_10PIN_JST")
      (description "CONNECTOR")
      (libsource (lib "MA_CONNECT_1") (part "CON 10"))
    )
    (comp (ref "X16")
      (value "EM / DL / CAN")
      (footprint "CON-MOLEX-53047-1010")
      (description "CONNECTOR")
      (libsource (lib "") (part "CON 10_1"))
    )
    (comp (ref "X17")
      (value "TEMP")
      (footprint "CON-PH_4PIN_JST")
      (description "CONNECTOR")
      (libsource (lib "MA_CONNECT_1") (part "CON 4"))
    )
    (comp (ref "X18")
      (value "VALVE2")
      (footprint "CON_3.0_2X_V_DUAL ROW")
      (description "Male 2mm Vertical Header 2 Pin")
      (libsource (lib "") (part "CON2_1"))
    )
    (comp (ref "X19")
      (value "SWD")
      (footprint "Mlk-pcb:CON-06-MALE-TH-2MM-VERTICAL")
      (description "Male 2.54mm Vertical Header 6 Pin")
      (fields (field (name "PART NUMBER") "100mil Header 1x6") (field (name "VOLTAGE") "250V"))
      (libsource (lib "Fotona") (part "CON6"))
    )
    (comp (ref "X20")
      (value "FAN2")
      (footprint "MOLEX_47053-1000")
      (description "CONNECTOR")
      (libsource (lib "MA_CONNECT_1") (part "CON 4"))
    )
    (comp (ref "X21")
      (value "BATT")
      (footprint "CON-MOLEX-53047-0210")
      (description "Right Angle Header SMD 2 pin")
      (libsource (lib "Fotona") (part "CON2"))
    )
  )
  (nets
    (net (code "1") (name "+3V3") (class "Default")
      (node (ref "C34") (pin "1") (pintype "passive"))
      (node (ref "C35") (pin "1") (pintype "passive"))
      (node (ref "C36") (pin "1") (pintype "passive"))
      (node (ref "C38") (pin "2") (pintype "passive"))
      (node (ref "C39") (pin "2") (pintype "passive"))
      (node (ref "C4") (pin "2") (pintype "passive"))
      (node (ref "C40") (pin "2") (pintype "passive"))
      (node (ref "IC1") (pin "3") (pinfunction "OUT_3") (pintype "power_in"))
      (node (ref "IC8") (pin "100") (pinfunction "Vdd_3_100") (pintype "power_in"))
      (node (ref "IC8") (pin "11") (pinfunction "Vdd_5_11") (pintype "power_in"))
      (node (ref "IC8") (pin "19") (pinfunction "Vdd12_19") (pintype "power_in"))
      (node (ref "IC8") (pin "28") (pinfunction "Vdd_4_28") (pintype "power_in"))
      (node (ref "IC8") (pin "50") (pinfunction "Vdd_1_50") (pintype "power_in"))
      (node (ref "IC8") (pin "75") (pinfunction "Vdd_2_75") (pintype "power_in"))
      (node (ref "V10") (pin "3") (pinfunction "K_3") (pintype "passive"))
      (node (ref "V12") (pin "2") (pinfunction "A2_2") (pintype "passive"))
      (node (ref "V13") (pin "3") (pinfunction "K_3") (pintype "passive"))
      (node (ref "V3") (pin "E") (pinfunction "E_E") (pintype "passive"))
      (node (ref "V9") (pin "3") (pinfunction "K_3") (pintype "passive"))
      (node (ref "X19") (pin "1") (pinfunction "1_1") (pintype "passive"))
    )
    (net (code "2") (name "+5V") (class "Default")
      (node (ref "A2") (pin "5") (pinfunction "Vout_5") (pintype "passive"))
      (node (ref "C15") (pin "2") (pintype "passive"))
      (node (ref "C18") (pin "2") (pintype "passive"))
      (node (ref "C27") (pin "1") (pintype "passive"))
      (node (ref "C3") (pin "2") (pintype "passive"))
      (node (ref "C30") (pin "2") (pintype "passive"))
      (node (ref "C46") (pin "1") (pintype "passive"))
      (node (ref "C59") (pin "P") (pinfunction "P_P") (pintype "passive"))
      (node (ref "C9") (pin "2") (pintype "passive"))
      (node (ref "H1") (pin "A") (pintype "passive"))
      (node (ref "H2") (pin "A") (pintype "passive"))
      (node (ref "H3") (pin "A") (pintype "passive"))
      (node (ref "H4") (pin "A") (pintype "passive"))
      (node (ref "H5") (pin "A") (pintype "passive"))
      (node (ref "H6") (pin "A") (pintype "passive"))
      (node (ref "H7") (pin "A") (pintype "passive"))
      (node (ref "H8") (pin "A") (pintype "passive"))
      (node (ref "IC1") (pin "1") (pinfunction "IN_1") (pintype "power_in"))
      (node (ref "IC10") (pin "16") (pinfunction "VCC_16") (pintype "power_in"))
      (node (ref "IC3") (pin "3") (pinfunction "VCC_3") (pintype "power_in"))
      (node (ref "IC4") (pin "6") (pinfunction "VDD_6") (pintype "power_in"))
      (node (ref "IC6") (pin "8") (pinfunction "VCC_8") (pintype "power_in"))
      (node (ref "JP1") (pin "2") (pintype "passive"))
      (node (ref "L19") (pin "2") (pinfunction "2_2") (pintype "passive"))
      (node (ref "R15") (pin "1") (pintype "passive"))
      (node (ref "R42") (pin "1") (pintype "passive"))
      (node (ref "V15") (pin "2") (pinfunction "A2_2") (pintype "passive"))
      (node (ref "X16") (pin "7") (pinfunction "7_7") (pintype "passive"))
      (node (ref "X3") (pin "1") (pinfunction "1_1") (pintype "passive"))
      (node (ref "X4") (pin "1") (pinfunction "1_1") (pintype "passive"))
      (node (ref "X6") (pin "1") (pinfunction "1_1") (pintype "passive"))
      (node (ref "X7") (pin "1") (pinfunction "1_1") (pintype "passive"))
    )
    (net (code "3") (name "+5VA") (class "Default")
      (node (ref "B1") (pin "2") (pinfunction "Vs_2") (pintype "passive"))
      (node (ref "B2") (pin "2") (pinfunction "Vs_2") (pintype "passive"))
      (node (ref "B3") (pin "2") (pinfunction "Vs_2") (pintype "passive"))
      (node (ref "B4") (pin "2") (pinfunction "Vs_2") (pintype "passive"))
      (node (ref "C13") (pin "1") (pintype "passive"))
      (node (ref "C26") (pin "1") (pintype "passive"))
      (node (ref "C49") (pin "1") (pintype "passive"))
      (node (ref "C51") (pin "1") (pintype "passive"))
      (node (ref "C53") (pin "1") (pintype "passive"))
      (node (ref "C55") (pin "1") (pintype "passive"))
      (node (ref "IC11") (pin "4") (pinfunction "OUT_4") (pintype "output"))
    )
    (net (code "4") (name "+12V") (class "Default")
      (node (ref "A1") (pin "5") (pinfunction "Vout_5") (pintype "passive"))
      (node (ref "C2") (pin "2") (pintype "passive"))
      (node (ref "F2") (pin "1") (pintype "passive"))
      (node (ref "JMP2") (pin "3") (pintype "passive"))
      (node (ref "R64") (pin "2") (pintype "passive"))
      (node (ref "X2") (pin "1") (pinfunction "1_1") (pintype "passive"))
    )
    (net (code "5") (name "/12Voff") (class "Default")
      (node (ref "IC8") (pin "92") (pinfunction "PB6//I2C1_SCL_92") (pintype "bidirectional"))
      (node (ref "R5") (pin "1") (pintype "passive"))
    )
    (net (code "6") (name "/AUDIO GND") (class "Default")
      (node (ref "C17") (pin "2") (pintype "passive"))
      (node (ref "X13") (pin "4") (pinfunction "4_4") (pintype "passive"))
    )
    (net (code "7") (name "/AUDIO IN1") (class "Default")
      (node (ref "C16") (pin "2") (pintype "passive"))
      (node (ref "X13") (pin "3") (pinfunction "3_3") (pintype "passive"))
    )
    (net (code "8") (name "/AUDIO IN2") (class "Default")
      (node (ref "X13") (pin "5") (pinfunction "5_5") (pintype "passive"))
    )
    (net (code "9") (name "/BOOT0") (class "Default")
      (node (ref "IC5") (pin "14") (pinfunction "CBUS3_14") (pintype "passive"))
      (node (ref "IC8") (pin "94") (pinfunction "BOOT0_94") (pintype "bidirectional"))
      (node (ref "R49") (pin "1") (pintype "passive"))
    )
    (net (code "10") (name "/BOOT1") (class "Default")
      (node (ref "IC8") (pin "37") (pinfunction "PB2/Boot1_37") (pintype "bidirectional"))
      (node (ref "R48") (pin "2") (pintype "passive"))
    )
    (net (code "11") (name "/CANH") (class "Default")
      (node (ref "IC3") (pin "7") (pinfunction "CANH_7") (pintype "passive"))
      (node (ref "R12") (pin "1") (pintype "passive"))
      (node (ref "X13") (pin "1") (pinfunction "1_1") (pintype "passive"))
      (node (ref "X16") (pin "1") (pinfunction "1_1") (pintype "passive"))
      (node (ref "X6") (pin "3") (pinfunction "3_3") (pintype "passive"))
      (node (ref "X7") (pin "3") (pinfunction "3_3") (pintype "passive"))
    )
    (net (code "12") (name "/CANL") (class "Default")
      (node (ref "IC3") (pin "6") (pinfunction "CANL_6") (pintype "passive"))
      (node (ref "R13") (pin "1") (pintype "passive"))
      (node (ref "X13") (pin "2") (pinfunction "2_2") (pintype "passive"))
      (node (ref "X16") (pin "3") (pinfunction "3_3") (pintype "passive"))
      (node (ref "X6") (pin "5") (pinfunction "5_5") (pintype "passive"))
      (node (ref "X7") (pin "5") (pinfunction "5_5") (pintype "passive"))
    )
    (net (code "13") (name "/CAN_RX") (class "Default")
      (node (ref "IC3") (pin "4") (pinfunction "RX_4") (pintype "output"))
      (node (ref "IC8") (pin "91") (pinfunction "PB5/CAN2_RX_91") (pintype "bidirectional"))
    )
    (net (code "14") (name "/CAN_TX") (class "Default")
      (node (ref "IC3") (pin "1") (pinfunction "TX_1") (pintype "input"))
      (node (ref "IC8") (pin "52") (pinfunction "PB13/CAN2_TX_52") (pintype "bidirectional"))
    )
    (net (code "15") (name "/DIODEsense1") (class "Default")
      (node (ref "IC8") (pin "33") (pinfunction "PC4/ADC12_IN14_33") (pintype "bidirectional"))
      (node (ref "IC8") (pin "53") (pinfunction "PB14/TIM12_CH1_53") (pintype "bidirectional"))
      (node (ref "L13") (pin "1") (pinfunction "1_1") (pintype "passive"))
      (node (ref "V13") (pin "1") (pinfunction "A1_1") (pintype "passive"))
    )
    (net (code "16") (name "/DIODEsense2") (class "Default")
      (node (ref "IC8") (pin "34") (pinfunction "PC5/ADC12_IN15_34") (pintype "bidirectional"))
      (node (ref "IC8") (pin "54") (pinfunction "PB15/TIM12_CH2_54") (pintype "bidirectional"))
      (node (ref "L14") (pin "1") (pinfunction "1_1") (pintype "passive"))
      (node (ref "V13") (pin "2") (pinfunction "A2_2") (pintype "passive"))
    )
    (net (code "17") (name "/DIODEstop") (class "Default")
      (node (ref "L2") (pin "1") (pinfunction "1_1") (pintype "passive"))
      (node (ref "V6") (pin "C") (pinfunction "C_C") (pintype "passive"))
      (node (ref "X6") (pin "2") (pinfunction "2_2") (pintype "passive"))
      (node (ref "X7") (pin "2") (pinfunction "2_2") (pintype "passive"))
    )
    (net (code "18") (name "/DOUT1") (class "Default")
      (node (ref "IC10") (pin "14") (pinfunction "~{DOUT1}_14") (pintype "output"))
      (node (ref "X15") (pin "8") (pinfunction "8_8") (pintype "passive"))
    )
    (net (code "19") (name "/FAN1_tacho") (class "Default")
      (node (ref "IC8") (pin "4") (pinfunction "PE5/TIM9_CH1_4") (pintype "bidirectional"))
      (node (ref "L20") (pin "1") (pinfunction "1_1") (pintype "passive"))
      (node (ref "V1") (pin "4") (pinfunction "4_4") (pintype "passive"))
    )
    (net (code "20") (name "/FAN2_tacho") (class "Default")
      (node (ref "IC8") (pin "5") (pinfunction "PE6/TIM9_CH2_5") (pintype "bidirectional"))
      (node (ref "L17") (pin "1") (pinfunction "1_1") (pintype "passive"))
      (node (ref "V1") (pin "5") (pinfunction "5_5") (pintype "passive"))
    )
    (net (code "21") (name "/FAN_RPM") (class "Default")
      (node (ref "IC8") (pin "95") (pinfunction "PB8/TIM10_CH1_95") (pintype "bidirectional"))
      (node (ref "L22") (pin "1") (pinfunction "1_1") (pintype "passive"))
      (node (ref "R63") (pin "1") (pintype "passive"))
      (node (ref "V1") (pin "1") (pinfunction "1_1") (pintype "passive"))
    )
    (net (code "22") (name "/FOOTSWactive") (class "Default")
      (node (ref "R9") (pin "1") (pintype "passive"))
      (node (ref "X15") (pin "5") (pinfunction "5_5") (pintype "passive"))
      (node (ref "X16") (pin "6") (pinfunction "6_6") (pintype "passive"))
      (node (ref "X6") (pin "6") (pinfunction "6_6") (pintype "passive"))
      (node (ref "X7") (pin "6") (pinfunction "6_6") (pintype "passive"))
    )
    (net (code "23") (name "/LED_1") (class "Default")
      (node (ref "IC8") (pin "59") (pinfunction "PD12/TIM4_CH1_59") (pintype "bidirectional"))
      (node (ref "R50") (pin "1") (pintype "passive"))
    )
    (net (code "24") (name "/LED_2") (class "Default")
      (node (ref "IC8") (pin "60") (pinfunction "PD13/TIM4_CH2_60") (pintype "bidirectional"))
      (node (ref "R51") (pin "1") (pintype "passive"))
    )
    (net (code "25") (name "/LED_BLUE1") (class "Default")
      (node (ref "IC8") (pin "84") (pinfunction "PD3_84") (pintype "bidirectional"))
      (node (ref "R30") (pin "1") (pintype "passive"))
    )
    (net (code "26") (name "/LED_BLUE2") (class "Default")
      (node (ref "IC8") (pin "88") (pinfunction "PD7_88") (pintype "bidirectional"))
      (node (ref "R34") (pin "1") (pintype "passive"))
    )
    (net (code "27") (name "/LED_GREEN1") (class "Default")
      (node (ref "IC8") (pin "82") (pinfunction "PD1_82") (pintype "bidirectional"))
      (node (ref "R28") (pin "1") (pintype "passive"))
    )
    (net (code "28") (name "/LED_GREEN2") (class "Default")
      (node (ref "IC8") (pin "86") (pinfunction "PD5_86") (pintype "bidirectional"))
      (node (ref "R32") (pin "1") (pintype "passive"))
    )
    (net (code "29") (name "/LED_RED1") (class "Default")
      (node (ref "IC8") (pin "81") (pinfunction "PD0_81") (pintype "bidirectional"))
      (node (ref "R27") (pin "1") (pintype "passive"))
    )
    (net (code "30") (name "/LED_RED2") (class "Default")
      (node (ref "IC8") (pin "85") (pinfunction "PD4_85") (pintype "bidirectional"))
      (node (ref "R31") (pin "1") (pintype "passive"))
    )
    (net (code "31") (name "/LED_YELLOW1") (class "Default")
      (node (ref "IC8") (pin "83") (pinfunction "PD2_83") (pintype "bidirectional"))
      (node (ref "R29") (pin "1") (pintype "passive"))
    )
    (net (code "32") (name "/LED_YELLOW2") (class "Default")
      (node (ref "IC8") (pin "87") (pinfunction "PD6_87") (pintype "bidirectional"))
      (node (ref "R33") (pin "1") (pintype "passive"))
    )
    (net (code "33") (name "/MCO") (class "Default")
      (node (ref "C45") (pin "2") (pintype "passive"))
      (node (ref "G1") (pin "2") (pinfunction "OSC2_2") (pintype "passive"))
      (node (ref "IC8") (pin "12") (pinfunction "OSC_IN_12") (pintype "input"))
    )
    (net (code "34") (name "/NRST") (class "Default")
      (node (ref "C31") (pin "1") (pintype "passive"))
      (node (ref "IC5") (pin "13") (pinfunction "CBUS2_13") (pintype "passive"))
      (node (ref "IC8") (pin "14") (pinfunction "NRST_14") (pintype "bidirectional"))
      (node (ref "X19") (pin "5") (pinfunction "5_5") (pintype "passive"))
    )
    (net (code "35") (name "/PUMP_CSENSE") (class "Default")
      (node (ref "IC8") (pin "23") (pinfunction "PA0/ADC123_IN0_23") (pintype "bidirectional"))
      (node (ref "R6") (pin "2") (pintype "passive"))
      (node (ref "V3") (pin "B") (pinfunction "B_B") (pintype "passive"))
      (node (ref "V3") (pin "C") (pinfunction "C_C") (pintype "passive"))
    )
    (net (code "36") (name "/PUMP_RPM") (class "Default")
      (node (ref "IC6") (pin "5") (pintype "input"))
      (node (ref "IC8") (pin "29") (pinfunction "PA4/DAC_OUT1/ADC12_IN4_29") (pintype "bidirectional"))
      (node (ref "R4") (pin "2") (pintype "passive"))
    )
    (net (code "37") (name "/PUMP_tacho") (class "Default")
      (node (ref "IC8") (pin "31") (pinfunction "PA6/ADC12_IN6/TIM3_CH1_31") (pintype "bidirectional"))
      (node (ref "V8") (pin "C") (pintype "passive"))
    )
    (net (code "38") (name "/Psense0") (class "Default")
      (node (ref "C50") (pin "1") (pintype "passive"))
      (node (ref "IC8") (pin "15") (pinfunction "PC0/ADC123_IN10_15") (pintype "bidirectional"))
      (node (ref "R55") (pin "1") (pintype "passive"))
      (node (ref "R56") (pin "2") (pintype "passive"))
    )
    (net (code "39") (name "/Psense1") (class "Default")
      (node (ref "C52") (pin "1") (pintype "passive"))
      (node (ref "IC8") (pin "16") (pinfunction "PC1/ADC123_IN11_16") (pintype "bidirectional"))
      (node (ref "R57") (pin "1") (pintype "passive"))
      (node (ref "R58") (pin "2") (pintype "passive"))
    )
    (net (code "40") (name "/Psense2") (class "Default")
      (node (ref "C54") (pin "1") (pintype "passive"))
      (node (ref "IC8") (pin "17") (pinfunction "PC2/ADC123_IN12_17") (pintype "bidirectional"))
      (node (ref "R59") (pin "1") (pintype "passive"))
      (node (ref "R60") (pin "2") (pintype "passive"))
    )
    (net (code "41") (name "/Psense3") (class "Default")
      (node (ref "C56") (pin "1") (pintype "passive"))
      (node (ref "IC8") (pin "18") (pinfunction "PC3/ADC123_IN13_18") (pintype "bidirectional"))
      (node (ref "R61") (pin "1") (pintype "passive"))
      (node (ref "R62") (pin "2") (pintype "passive"))
    )
    (net (code "42") (name "/RIN1") (class "Default")
      (node (ref "IC10") (pin "13") (pinfunction "RIN1_13") (pintype "input"))
      (node (ref "X15") (pin "7") (pinfunction "7_7") (pintype "passive"))
    )
    (net (code "43") (name "/SWCLK") (class "Default")
      (node (ref "IC8") (pin "76") (pinfunction "PA14_76") (pintype "bidirectional"))
      (node (ref "X19") (pin "2") (pinfunction "2_2") (pintype "passive"))
    )
    (net (code "44") (name "/SWDIO") (class "Default")
      (node (ref "IC8") (pin "72") (pinfunction "PA13_72") (pintype "bidirectional"))
      (node (ref "X19") (pin "4") (pinfunction "4_4") (pintype "passive"))
    )
    (net (code "45") (name "/SWO") (class "Default")
      (node (ref "IC8") (pin "89") (pinfunction "PB3/TIM2_CH2_89") (pintype "bidirectional"))
      (node (ref "X19") (pin "6") (pinfunction "6_6") (pintype "passive"))
    )
    (net (code "46") (name "/SYS_SHG") (class "Default")
      (node (ref "IC8") (pin "90") (pinfunction "PB4_90") (pintype "bidirectional"))
      (node (ref "R14") (pin "2") (pintype "passive"))
    )
    (net (code "47") (name "/TIM1_CH1") (class "Default")
      (node (ref "IC7") (pin "4") (pinfunction "I3_4") (pintype "passive"))
      (node (ref "IC8") (pin "40") (pinfunction "PE9/TIM1_CH1_40") (pintype "bidirectional"))
    )
    (net (code "48") (name "/TIM1_CH2") (class "Default")
      (node (ref "IC7") (pin "3") (pinfunction "I2_3") (pintype "passive"))
      (node (ref "IC8") (pin "42") (pinfunction "PE11/TIM1_CH2_42") (pintype "bidirectional"))
    )
    (net (code "49") (name "/TIM1_CH3") (class "Default")
      (node (ref "IC7") (pin "2") (pinfunction "I1_2") (pintype "passive"))
      (node (ref "IC8") (pin "44") (pinfunction "PE13/TIM1_CH3_44") (pintype "bidirectional"))
    )
    (net (code "50") (name "/TIM1_CH4") (class "Default")
      (node (ref "IC7") (pin "1") (pinfunction "I0_1") (pintype "passive"))
      (node (ref "IC8") (pin "45") (pinfunction "PE14/TIM1_CH4_45") (pintype "bidirectional"))
    )
    (net (code "51") (name "/TIM8_CH1") (class "Default")
      (node (ref "IC7") (pin "5") (pinfunction "I4_5") (pintype "passive"))
      (node (ref "IC8") (pin "63") (pinfunction "PC6/TIM8_CH1_63") (pintype "bidirectional"))
    )
    (net (code "52") (name "/TIM8_CH2") (class "Default")
      (node (ref "IC7") (pin "6") (pinfunction "I5_6") (pintype "passive"))
      (node (ref "IC8") (pin "64") (pinfunction "PC7/TIM8_CH2_64") (pintype "bidirectional"))
    )
    (net (code "53") (name "/TIM8_CH3") (class "Default")
      (node (ref "IC7") (pin "7") (pinfunction "I6_7") (pintype "passive"))
      (node (ref "IC8") (pin "65") (pinfunction "PC8/TIM8_CH3_65") (pintype "bidirectional"))
    )
    (net (code "54") (name "/TIM8_CH4") (class "Default")
      (node (ref "IC7") (pin "8") (pinfunction "I7_8") (pintype "passive"))
      (node (ref "IC8") (pin "66") (pinfunction "PC9/TIM8_CH4_66") (pintype "bidirectional"))
    )
    (net (code "55") (name "/TempH2O_1") (class "Default")
      (node (ref "C47") (pin "1") (pintype "passive"))
      (node (ref "IC8") (pin "24") (pinfunction "PA1/ADC123_IN1_24") (pintype "bidirectional"))
      (node (ref "R53") (pin "1") (pintype "passive"))
      (node (ref "X17") (pin "1") (pinfunction "1_1") (pintype "passive"))
    )
    (net (code "56") (name "/TempH2O_2") (class "Default")
      (node (ref "C48") (pin "1") (pintype "passive"))
      (node (ref "IC8") (pin "25") (pinfunction "PA2/ADC123_IN2_25") (pintype "bidirectional"))
      (node (ref "R54") (pin "1") (pintype "passive"))
      (node (ref "X17") (pin "3") (pinfunction "3_3") (pintype "passive"))
    )
    (net (code "57") (name "/UART0_RXD") (class "Default")
      (node (ref "JP2") (pin "1") (pintype "passive"))
      (node (ref "X13") (pin "7") (pinfunction "7_7") (pintype "passive"))
    )
    (net (code "58") (name "/UART0_TXD") (class "Default")
      (node (ref "JP3") (pin "1") (pintype "passive"))
      (node (ref "X13") (pin "8") (pinfunction "8_8") (pintype "passive"))
    )
    (net (code "59") (name "/USART1_RX") (class "Default")
      (node (ref "IC8") (pin "69") (pinfunction "PA10/USART1_RX_69") (pintype "bidirectional"))
      (node (ref "JP2") (pin "3") (pintype "passive"))
    )
    (net (code "60") (name "/USART1_TX") (class "Default")
      (node (ref "IC8") (pin "68") (pinfunction "PA9/USART1_TX_68") (pintype "bidirectional"))
      (node (ref "JP3") (pin "3") (pintype "passive"))
    )
    (net (code "61") (name "/USART3_RX") (class "Default")
      (node (ref "IC10") (pin "12") (pinfunction "~{ROUT1}_12") (pintype "output"))
      (node (ref "IC8") (pin "79") (pinfunction "PC11/USART3_RX_79") (pintype "bidirectional"))
    )
    (net (code "62") (name "/USART3_TX") (class "Default")
      (node (ref "IC10") (pin "11") (pinfunction "DIN1_11") (pintype "input"))
      (node (ref "IC8") (pin "78") (pinfunction "PC10/USART3_TX_78") (pintype "bidirectional"))
    )
    (net (code "63") (name "/USBDM") (class "Default")
      (node (ref "C22") (pin "2") (pintype "passive"))
      (node (ref "IC5") (pin "16") (pinfunction "USBDM_16") (pintype "passive"))
      (node (ref "R20") (pin "1") (pintype "passive"))
    )
    (net (code "64") (name "/USBDP") (class "Default")
      (node (ref "C24") (pin "1") (pintype "passive"))
      (node (ref "IC5") (pin "15") (pinfunction "USBDP_15") (pintype "passive"))
      (node (ref "R21") (pin "1") (pintype "passive"))
    )
    (net (code "65") (name "/USBPWR#") (class "Default")
      (node (ref "IC5") (pin "12") (pinfunction "CBUS4_12") (pintype "passive"))
      (node (ref "R26") (pin "2") (pintype "passive"))
    )
    (net (code "66") (name "/USB_RXLED") (class "Default")
      (node (ref "IC5") (pin "22") (pinfunction "CBUS1_22") (pintype "passive"))
      (node (ref "R25") (pin "2") (pintype "passive"))
    )
    (net (code "67") (name "/USB_TXLED") (class "Default")
      (node (ref "IC5") (pin "23") (pinfunction "CBUS0_23") (pintype "passive"))
      (node (ref "R24") (pin "2") (pintype "passive"))
    )
    (net (code "68") (name "/cwbBUTTON") (class "Default")
      (node (ref "L12") (pin "1") (pinfunction "1_1") (pintype "passive"))
      (node (ref "R36") (pin "1") (pintype "passive"))
      (node (ref "V11") (pin "1") (pinfunction "1_1") (pintype "passive"))
      (node (ref "V6") (pin "E") (pinfunction "E_E") (pintype "passive"))
    )
    (net (code "69") (name "/cwbDOOR") (class "Default")
      (node (ref "L1") (pin "1") (pinfunction "1_1") (pintype "passive"))
      (node (ref "L16") (pin "1") (pinfunction "1_1") (pintype "passive"))
      (node (ref "R37") (pin "1") (pintype "passive"))
      (node (ref "V11") (pin "3") (pinfunction "3_3") (pintype "passive"))
      (node (ref "V4") (pin "1") (pinfunction "1_1") (pintype "passive"))
    )
    (net (code "70") (name "/cwbENGM") (class "Default")
      (node (ref "L15") (pin "1") (pinfunction "1_1") (pintype "passive"))
      (node (ref "L21") (pin "1") (pinfunction "1_1") (pintype "passive"))
      (node (ref "R38") (pin "1") (pintype "passive"))
      (node (ref "V4") (pin "3") (pinfunction "3_3") (pintype "passive"))
    )
    (net (code "71") (name "24V") (class "Default")
      (node (ref "A1") (pin "2") (pinfunction "Vin_2") (pintype "passive"))
      (node (ref "A2") (pin "2") (pinfunction "Vin_2") (pintype "passive"))
      (node (ref "C1") (pin "1") (pintype "passive"))
      (node (ref "C25") (pin "1") (pintype "passive"))
      (node (ref "C29") (pin "1") (pintype "passive"))
      (node (ref "F1") (pin "2") (pinfunction "2_2") (pintype "passive"))
      (node (ref "IC7") (pin "10") (pinfunction "PWR_10") (pintype "passive"))
      (node (ref "JMP2") (pin "1") (pintype "passive"))
      (node (ref "R46") (pin "2") (pintype "passive"))
      (node (ref "R7") (pin "2") (pintype "passive"))
      (node (ref "X10") (pin "5") (pinfunction "5_5") (pintype "passive"))
      (node (ref "X11") (pin "2") (pinfunction "2_2") (pintype "passive"))
      (node (ref "X11") (pin "4") (pinfunction "4_4") (pintype "passive"))
      (node (ref "X11") (pin "6") (pinfunction "6_6") (pintype "passive"))
      (node (ref "X11") (pin "8") (pinfunction "8_8") (pintype "passive"))
      (node (ref "X12") (pin "2") (pinfunction "2_2") (pintype "passive"))
      (node (ref "X12") (pin "4") (pinfunction "4_4") (pintype "passive"))
      (node (ref "X12") (pin "6") (pinfunction "6_6") (pintype "passive"))
      (node (ref "X18") (pin "1") (pinfunction "1_1") (pintype "passive"))
    )
    (net (code "72") (name "Agnd") (class "Default")
      (node (ref "B1") (pin "3") (pinfunction "GND_3") (pintype "passive"))
      (node (ref "B2") (pin "3") (pinfunction "GND_3") (pintype "passive"))
      (node (ref "B3") (pin "3") (pinfunction "GND_3") (pintype "passive"))
      (node (ref "B4") (pin "3") (pinfunction "GND_3") (pintype "passive"))
      (node (ref "C12") (pin "2") (pintype "passive"))
      (node (ref "C26") (pin "2") (pintype "passive"))
      (node (ref "C41") (pin "2") (pintype "passive"))
      (node (ref "C42") (pin "2") (pintype "passive"))
      (node (ref "C43") (pin "2") (pintype "passive"))
      (node (ref "C47") (pin "2") (pintype "passive"))
      (node (ref "C48") (pin "2") (pintype "passive"))
      (node (ref "C49") (pin "2") (pintype "passive"))
      (node (ref "C50") (pin "2") (pintype "passive"))
      (node (ref "C51") (pin "2") (pintype "passive"))
      (node (ref "C52") (pin "2") (pintype "passive"))
      (node (ref "C53") (pin "2") (pintype "passive"))
      (node (ref "C54") (pin "2") (pintype "passive"))
      (node (ref "C55") (pin "2") (pintype "passive"))
      (node (ref "C56") (pin "2") (pintype "passive"))
      (node (ref "IC11") (pin "1") (pinfunction "GND_1") (pintype "passive"))
      (node (ref "IC8") (pin "20") (pinfunction "VssA_20") (pintype "input"))
      (node (ref "IC9") (pin "3") (pinfunction "GND_3") (pintype "power_in"))
      (node (ref "JMP1") (pin "2") (pinfunction "2_2") (pintype "passive"))
      (node (ref "R43") (pin "1") (pintype "passive"))
      (node (ref "R45") (pin "2") (pintype "passive"))
      (node (ref "R47") (pin "1") (pintype "passive"))
      (node (ref "R56") (pin "1") (pintype "passive"))
      (node (ref "R58") (pin "1") (pintype "passive"))
      (node (ref "R60") (pin "1") (pintype "passive"))
      (node (ref "R62") (pin "1") (pintype "passive"))
      (node (ref "X17") (pin "2") (pinfunction "2_2") (pintype "passive"))
      (node (ref "X17") (pin "4") (pinfunction "4_4") (pintype "passive"))
    )
    (net (code "73") (name "EARTH") (class "Default")
      (node (ref "JMP1") (pin "4") (pinfunction "4_4") (pintype "passive"))
      (node (ref "TP1") (pin "1") (pinfunction "1_1") (pintype "passive"))
      (node (ref "TP2") (pin "1") (pinfunction "1_1") (pintype "passive"))
    )
    (net (code "74") (name "GND") (class "Default")
      (node (ref "C10") (pin "2") (pintype "passive"))
      (node (ref "C11") (pin "2") (pintype "passive"))
      (node (ref "C14") (pin "1") (pintype "passive"))
      (node (ref "C15") (pin "1") (pintype "passive"))
      (node (ref "C18") (pin "1") (pintype "passive"))
      (node (ref "C19") (pin "2") (pintype "passive"))
      (node (ref "C20") (pin "2") (pintype "passive"))
      (node (ref "C21") (pin "1") (pintype "passive"))
      (node (ref "C22") (pin "1") (pintype "passive"))
      (node (ref "C23") (pin "1") (pintype "passive"))
      (node (ref "C24") (pin "2") (pintype "passive"))
      (node (ref "C27") (pin "2") (pintype "passive"))
      (node (ref "C3") (pin "1") (pintype "passive"))
      (node (ref "C30") (pin "1") (pintype "passive"))
      (node (ref "C31") (pin "2") (pintype "passive"))
      (node (ref "C32") (pin "2") (pintype "passive"))
      (node (ref "C33") (pin "2") (pintype "passive"))
      (node (ref "C34") (pin "2") (pintype "passive"))
      (node (ref "C35") (pin "2") (pintype "passive"))
      (node (ref "C36") (pin "2") (pintype "passive"))
      (node (ref "C37") (pin "2") (pintype "passive"))
      (node (ref "C38") (pin "1") (pintype "passive"))
      (node (ref "C39") (pin "1") (pintype "passive"))
      (node (ref "C4") (pin "1") (pintype "passive"))
      (node (ref "C40") (pin "1") (pintype "passive"))
      (node (ref "C44") (pin "1") (pintype "passive"))
      (node (ref "C45") (pin "1") (pintype "passive"))
      (node (ref "C46") (pin "2") (pintype "passive"))
      (node (ref "C57") (pin "2") (pintype "passive"))
      (node (ref "C58") (pin "2") (pintype "passive"))
      (node (ref "C59") (pin "M") (pinfunction "M_M") (pintype "passive"))
      (node (ref "C7") (pin "1") (pintype "passive"))
      (node (ref "C8") (pin "1") (pintype "passive"))
      (node (ref "C9") (pin "1") (pintype "passive"))
      (node (ref "G3") (pin "M") (pinfunction "-_M") (pintype "passive"))
      (node (ref "IC1") (pin "2") (pinfunction "GND_2") (pintype "power_in"))
      (node (ref "IC10") (pin "15") (pinfunction "GND_15") (pintype "power_in"))
      (node (ref "IC2") (pin "11") (pinfunction "E_11") (pintype "passive"))
      (node (ref "IC2") (pin "13") (pinfunction "E_13") (pintype "passive"))
      (node (ref "IC2") (pin "15") (pinfunction "E_15") (pintype "passive"))
      (node (ref "IC2") (pin "9") (pinfunction "E_9") (pintype "passive"))
      (node (ref "IC3") (pin "2") (pinfunction "GND_2") (pintype "power_in"))
      (node (ref "IC3") (pin "8") (pinfunction "STB_8") (pintype "input"))
      (node (ref "IC4") (pin "2") (pinfunction "NC_2") (pintype "passive"))
      (node (ref "IC4") (pin "7") (pinfunction "GND_7") (pintype "power_in"))
      (node (ref "IC4") (pin "9") (pinfunction "EP_9") (pintype "power_in"))
      (node (ref "IC5") (pin "18") (pinfunction "GND_18") (pintype "passive"))
      (node (ref "IC5") (pin "21") (pinfunction "GND_21") (pintype "passive"))
      (node (ref "IC5") (pin "25") (pinfunction "AGND_25") (pintype "passive"))
      (node (ref "IC5") (pin "26") (pinfunction "TEST_26") (pintype "passive"))
      (node (ref "IC5") (pin "7") (pinfunction "GND_7") (pintype "passive"))
      (node (ref "IC6") (pin "4") (pinfunction "VEE_4") (pintype "power_in"))
      (node (ref "IC8") (pin "10") (pinfunction "Vss_5_10") (pintype "power_in"))
      (node (ref "IC8") (pin "27") (pinfunction "Vss_4_27") (pintype "power_in"))
      (node (ref "IC8") (pin "74") (pinfunction "Vss_2_74") (pintype "power_in"))
      (node (ref "IC8") (pin "99") (pinfunction "RFU_99") (pintype "passive"))
      (node (ref "JMP1") (pin "5") (pinfunction "5_5") (pintype "passive"))
      (node (ref "R23") (pin "1") (pintype "passive"))
      (node (ref "R3") (pin "2") (pintype "passive"))
      (node (ref "R4") (pin "1") (pintype "passive"))
      (node (ref "R48") (pin "1") (pintype "passive"))
      (node (ref "R49") (pin "2") (pintype "passive"))
      (node (ref "V11") (pin "2") (pinfunction "2_2") (pintype "passive"))
      (node (ref "V4") (pin "2") (pinfunction "2_2") (pintype "passive"))
      (node (ref "V7") (pin "2") (pinfunction "2_2") (pintype "passive"))
      (node (ref "X13") (pin "6") (pinfunction "6_6") (pintype "passive"))
      (node (ref "X16") (pin "4") (pinfunction "4_4") (pintype "passive"))
      (node (ref "X19") (pin "3") (pinfunction "3_3") (pintype "passive"))
      (node (ref "X21") (pin "2") (pinfunction "2_2") (pintype "passive"))
      (node (ref "X3") (pin "3") (pinfunction "3_3") (pintype "passive"))
      (node (ref "X4") (pin "3") (pinfunction "3_3") (pintype "passive"))
      (node (ref "X6") (pin "4") (pinfunction "4_4") (pintype "passive"))
      (node (ref "X7") (pin "4") (pinfunction "4_4") (pintype "passive"))
      (node (ref "X9") (pin "5") (pinfunction "5_5") (pintype "passive"))
      (node (ref "X9") (pin "6") (pinfunction "6_6") (pintype "passive"))
    )
    (net (code "75") (name "Net-(A1-ON{slash}OFF)") (class "Default")
      (node (ref "A1") (pin "1") (pinfunction "ON/OFF_1") (pintype "passive"))
      (node (ref "V2") (pin "C") (pintype "passive"))
    )
    (net (code "76") (name "Net-(A1-TRIM)") (class "Default")
      (node (ref "A1") (pin "4") (pinfunction "TRIM_4") (pintype "passive"))
      (node (ref "R1") (pin "1") (pintype "passive"))
    )
    (net (code "77") (name "Net-(B1-OUT)") (class "Default")
      (node (ref "B1") (pin "4") (pinfunction "OUT_4") (pintype "passive"))
      (node (ref "R55") (pin "2") (pintype "passive"))
    )
    (net (code "78") (name "Net-(B2-OUT)") (class "Default")
      (node (ref "B2") (pin "4") (pinfunction "OUT_4") (pintype "passive"))
      (node (ref "R57") (pin "2") (pintype "passive"))
    )
    (net (code "79") (name "Net-(B3-OUT)") (class "Default")
      (node (ref "B3") (pin "4") (pinfunction "OUT_4") (pintype "passive"))
      (node (ref "R59") (pin "2") (pintype "passive"))
    )
    (net (code "80") (name "Net-(B4-OUT)") (class "Default")
      (node (ref "B4") (pin "4") (pinfunction "OUT_4") (pintype "passive"))
      (node (ref "R61") (pin "2") (pintype "passive"))
    )
    (net (code "81") (name "Net-(C10-Pad1)") (class "Default")
      (node (ref "C10") (pin "1") (pintype "passive"))
      (node (ref "R50") (pin "2") (pintype "passive"))
      (node (ref "X3") (pin "2") (pinfunction "2_2") (pintype "passive"))
    )
    (net (code "82") (name "Net-(C11-Pad1)") (class "Default")
      (node (ref "C11") (pin "1") (pintype "passive"))
      (node (ref "R51") (pin "2") (pintype "passive"))
      (node (ref "X4") (pin "2") (pinfunction "2_2") (pintype "passive"))
    )
    (net (code "83") (name "Net-(C19-Pad1)") (class "Default")
      (node (ref "C19") (pin "1") (pintype "passive"))
      (node (ref "L3") (pin "1") (pinfunction "1_1") (pintype "passive"))
      (node (ref "R22") (pin "1") (pintype "passive"))
      (node (ref "V7") (pin "4") (pinfunction "4_4") (pintype "passive"))
      (node (ref "X9") (pin "1") (pinfunction "1_1") (pintype "passive"))
    )
    (net (code "84") (name "Net-(C28-Pad1)") (class "Default")
      (node (ref "C28") (pin "1") (pintype "passive"))
      (node (ref "IC6") (pin "1") (pintype "output"))
      (node (ref "R41") (pin "2") (pintype "passive"))
      (node (ref "R6") (pin "1") (pintype "passive"))
    )
    (net (code "85") (name "Net-(C28-Pad2)") (class "Default")
      (node (ref "C28") (pin "2") (pintype "passive"))
      (node (ref "IC6") (pin "2") (pintype "input"))
      (node (ref "R40") (pin "2") (pintype "passive"))
      (node (ref "R41") (pin "1") (pintype "passive"))
    )
    (net (code "86") (name "Net-(F1-Pad1)") (class "Default")
      (node (ref "F1") (pin "1") (pinfunction "1_1") (pintype "passive"))
      (node (ref "X1") (pin "1") (pinfunction "1_1") (pintype "passive"))
      (node (ref "X1") (pin "3") (pinfunction "3_3") (pintype "passive"))
    )
    (net (code "87") (name "Net-(F2-Pad2)") (class "Default")
      (node (ref "F2") (pin "2") (pintype "passive"))
      (node (ref "IC2") (pin "1") (pinfunction "A_1") (pintype "passive"))
      (node (ref "IC2") (pin "3") (pinfunction "A_3") (pintype "passive"))
      (node (ref "IC2") (pin "5") (pinfunction "A_5") (pintype "passive"))
      (node (ref "IC2") (pin "7") (pinfunction "A_7") (pintype "passive"))
      (node (ref "R44") (pin "2") (pintype "passive"))
      (node (ref "X15") (pin "1") (pinfunction "1_1") (pintype "passive"))
    )
    (net (code "88") (name "Net-(G1-OSC1)") (class "Default")
      (node (ref "C44") (pin "2") (pintype "passive"))
      (node (ref "G1") (pin "1") (pinfunction "OSC1_1") (pintype "passive"))
      (node (ref "R52") (pin "1") (pintype "passive"))
    )
    (net (code "89") (name "Net-(G3-+)") (class "Default")
      (node (ref "G3") (pin "P") (pinfunction "+_P") (pintype "passive"))
      (node (ref "V12") (pin "1") (pinfunction "A1_1") (pintype "passive"))
      (node (ref "X21") (pin "1") (pinfunction "1_1") (pintype "passive"))
    )
    (net (code "90") (name "Net-(H1-PadK)") (class "Default")
      (node (ref "H1") (pin "K") (pintype "passive"))
      (node (ref "R27") (pin "2") (pintype "passive"))
    )
    (net (code "91") (name "Net-(H2-PadK)") (class "Default")
      (node (ref "H2") (pin "K") (pintype "passive"))
      (node (ref "R28") (pin "2") (pintype "passive"))
    )
    (net (code "92") (name "Net-(H3-PadK)") (class "Default")
      (node (ref "H3") (pin "K") (pintype "passive"))
      (node (ref "R29") (pin "2") (pintype "passive"))
    )
    (net (code "93") (name "Net-(H4-PadK)") (class "Default")
      (node (ref "H4") (pin "K") (pintype "passive"))
      (node (ref "R30") (pin "2") (pintype "passive"))
    )
    (net (code "94") (name "Net-(H5-PadK)") (class "Default")
      (node (ref "H5") (pin "K") (pintype "passive"))
      (node (ref "R31") (pin "2") (pintype "passive"))
    )
    (net (code "95") (name "Net-(H6-PadK)") (class "Default")
      (node (ref "H6") (pin "K") (pintype "passive"))
      (node (ref "R32") (pin "2") (pintype "passive"))
    )
    (net (code "96") (name "Net-(H7-PadK)") (class "Default")
      (node (ref "H7") (pin "K") (pintype "passive"))
      (node (ref "R33") (pin "2") (pintype "passive"))
    )
    (net (code "97") (name "Net-(H8-PadK)") (class "Default")
      (node (ref "H8") (pin "K") (pintype "passive"))
      (node (ref "R34") (pin "2") (pintype "passive"))
    )
    (net (code "98") (name "Net-(H9-PadK)") (class "Default")
      (node (ref "H9") (pin "K") (pinfunction "K_K") (pintype "passive"))
      (node (ref "R24") (pin "1") (pintype "passive"))
    )
    (net (code "99") (name "Net-(H10-PadK)") (class "Default")
      (node (ref "H10") (pin "K") (pinfunction "K_K") (pintype "passive"))
      (node (ref "R25") (pin "1") (pintype "passive"))
    )
    (net (code "100") (name "Net-(H11-PadK)") (class "Default")
      (node (ref "H11") (pin "K") (pinfunction "K_K") (pintype "passive"))
      (node (ref "R26") (pin "1") (pintype "passive"))
    )
    (net (code "101") (name "Net-(H12-PadA)") (class "Default")
      (node (ref "H12") (pin "A") (pintype "passive"))
      (node (ref "V5") (pin "A") (pintype "passive"))
    )
    (net (code "102") (name "Net-(IC2-K-Pad2)") (class "Default")
      (node (ref "IC2") (pin "2") (pinfunction "K_2") (pintype "passive"))
      (node (ref "R8") (pin "2") (pintype "passive"))
    )
    (net (code "103") (name "Net-(IC2-K-Pad4)") (class "Default")
      (node (ref "IC2") (pin "4") (pinfunction "K_4") (pintype "passive"))
      (node (ref "R9") (pin "2") (pintype "passive"))
    )
    (net (code "104") (name "Net-(IC2-K-Pad6)") (class "Default")
      (node (ref "IC2") (pin "6") (pinfunction "K_6") (pintype "passive"))
      (node (ref "R10") (pin "2") (pintype "passive"))
    )
    (net (code "105") (name "Net-(IC2-K-Pad8)") (class "Default")
      (node (ref "IC2") (pin "8") (pinfunction "K_8") (pintype "passive"))
      (node (ref "R11") (pin "2") (pintype "passive"))
    )
    (net (code "106") (name "Net-(IC3-SPLIT)") (class "Default")
      (node (ref "C14") (pin "2") (pintype "passive"))
      (node (ref "IC3") (pin "5") (pinfunction "SPLIT_5") (pintype "passive"))
      (node (ref "R12") (pin "2") (pintype "passive"))
      (node (ref "R13") (pin "2") (pintype "passive"))
    )
    (net (code "107") (name "Net-(IC4-IN+)") (class "Default")
      (node (ref "C16") (pin "1") (pintype "passive"))
      (node (ref "IC4") (pin "3") (pinfunction "IN+_3") (pintype "input"))
    )
    (net (code "108") (name "Net-(IC4-IN-)") (class "Default")
      (node (ref "C17") (pin "1") (pintype "passive"))
      (node (ref "IC4") (pin "4") (pinfunction "IN-_4") (pintype "input"))
    )
    (net (code "109") (name "Net-(IC4-OUT+)") (class "Default")
      (node (ref "IC4") (pin "5") (pinfunction "OUT+_5") (pintype "output"))
      (node (ref "X8") (pin "1") (pinfunction "1_1") (pintype "passive"))
    )
    (net (code "110") (name "Net-(IC4-OUT-)") (class "Default")
      (node (ref "IC4") (pin "8") (pinfunction "OUT-_8") (pintype "passive"))
      (node (ref "X8") (pin "3") (pinfunction "3_3") (pintype "passive"))
    )
    (net (code "111") (name "Net-(IC4-~{SD})") (class "Default")
      (node (ref "IC4") (pin "1") (pinfunction "~{SD}_1") (pintype "passive"))
      (node (ref "R15") (pin "2") (pintype "passive"))
    )
    (net (code "112") (name "Net-(IC5-RXD)") (class "Default")
      (node (ref "IC5") (pin "5") (pinfunction "RXD_5") (pintype "passive"))
      (node (ref "JP3") (pin "2") (pintype "passive"))
    )
    (net (code "113") (name "Net-(IC5-TXD)") (class "Default")
      (node (ref "IC5") (pin "1") (pinfunction "TXD_1") (pintype "passive"))
      (node (ref "JP2") (pin "2") (pintype "passive"))
    )
    (net (code "114") (name "Net-(IC5-VCC)") (class "Default")
      (node (ref "C20") (pin "1") (pintype "passive"))
      (node (ref "C21") (pin "2") (pintype "passive"))
      (node (ref "IC5") (pin "20") (pinfunction "VCC_20") (pintype "passive"))
      (node (ref "V15") (pin "3") (pinfunction "K_3") (pintype "passive"))
    )
    (net (code "115") (name "Net-(IC5-~{RESET})") (class "Default")
      (node (ref "IC5") (pin "19") (pinfunction "~{RESET}_19") (pintype "passive"))
      (node (ref "R22") (pin "2") (pintype "passive"))
      (node (ref "R23") (pin "2") (pintype "passive"))
    )
    (net (code "116") (name "Net-(IC6-Pad3)") (class "Default")
      (node (ref "IC6") (pin "3") (pintype "input"))
      (node (ref "R39") (pin "2") (pintype "passive"))
      (node (ref "X10") (pin "1") (pinfunction "1_1") (pintype "passive"))
    )
    (net (code "117") (name "Net-(IC6-Pad6)") (class "Default")
      (node (ref "IC6") (pin "6") (pintype "input"))
      (node (ref "R2") (pin "2") (pintype "passive"))
      (node (ref "R3") (pin "1") (pintype "passive"))
    )
    (net (code "118") (name "Net-(IC6-Pad7)") (class "Default")
      (node (ref "IC6") (pin "7") (pintype "output"))
      (node (ref "R2") (pin "1") (pintype "passive"))
      (node (ref "X10") (pin "4") (pinfunction "4_4") (pintype "passive"))
    )
    (net (code "119") (name "Net-(IC7-O0)") (class "Default")
      (node (ref "IC7") (pin "18") (pinfunction "O0_18") (pintype "passive"))
      (node (ref "L4") (pin "1") (pinfunction "1_1") (pintype "passive"))
    )
    (net (code "120") (name "Net-(IC7-O1)") (class "Default")
      (node (ref "IC7") (pin "17") (pinfunction "O1_17") (pintype "passive"))
      (node (ref "L5") (pin "1") (pinfunction "1_1") (pintype "passive"))
    )
    (net (code "121") (name "Net-(IC7-O2)") (class "Default")
      (node (ref "IC7") (pin "16") (pinfunction "O2_16") (pintype "passive"))
      (node (ref "L6") (pin "1") (pinfunction "1_1") (pintype "passive"))
    )
    (net (code "122") (name "Net-(IC7-O3)") (class "Default")
      (node (ref "IC7") (pin "15") (pinfunction "O3_15") (pintype "passive"))
      (node (ref "L7") (pin "1") (pinfunction "1_1") (pintype "passive"))
    )
    (net (code "123") (name "Net-(IC7-O4)") (class "Default")
      (node (ref "IC7") (pin "14") (pinfunction "O4_14") (pintype "passive"))
      (node (ref "L8") (pin "1") (pinfunction "1_1") (pintype "passive"))
    )
    (net (code "124") (name "Net-(IC7-O5)") (class "Default")
      (node (ref "IC7") (pin "13") (pinfunction "O5_13") (pintype "passive"))
      (node (ref "L9") (pin "1") (pinfunction "1_1") (pintype "passive"))
    )
    (net (code "125") (name "Net-(IC7-O6)") (class "Default")
      (node (ref "IC7") (pin "12") (pinfunction "O6_12") (pintype "passive"))
      (node (ref "L10") (pin "1") (pinfunction "1_1") (pintype "passive"))
    )
    (net (code "126") (name "Net-(IC7-O7)") (class "Default")
      (node (ref "IC7") (pin "11") (pinfunction "O7_11") (pintype "passive"))
      (node (ref "L11") (pin "1") (pinfunction "1_1") (pintype "passive"))
    )
    (net (code "127") (name "Net-(IC8-OSC_OUT)") (class "Default")
      (node (ref "IC8") (pin "13") (pinfunction "OSC_OUT_13") (pintype "output"))
      (node (ref "R52") (pin "2") (pintype "passive"))
    )
    (net (code "128") (name "Net-(IC8-PA3{slash}ADC123_IN3{slash})") (class "Default")
      (node (ref "IC8") (pin "26") (pinfunction "PA3/ADC123_IN3/_26") (pintype "bidirectional"))
      (node (ref "R42") (pin "2") (pintype "passive"))
      (node (ref "R43") (pin "2") (pintype "passive"))
      (node (ref "V9") (pin "1") (pinfunction "A1_1") (pintype "passive"))
    )
    (net (code "129") (name "Net-(IC8-PB0{slash}ADC12_IN8{slash}TIM3_CH3)") (class "Default")
      (node (ref "IC8") (pin "35") (pinfunction "PB0/ADC12_IN8/TIM3_CH3_35") (pintype "bidirectional"))
      (node (ref "R44") (pin "1") (pintype "passive"))
      (node (ref "R45") (pin "1") (pintype "passive"))
      (node (ref "V10") (pin "1") (pinfunction "A1_1") (pintype "passive"))
      (node (ref "V10") (pin "2") (pinfunction "A2_2") (pintype "passive"))
    )
    (net (code "130") (name "Net-(IC8-PB1{slash}ADC12_IN9{slash}TIM3_CH4)") (class "Default")
      (node (ref "IC8") (pin "36") (pinfunction "PB1/ADC12_IN9/TIM3_CH4_36") (pintype "bidirectional"))
      (node (ref "R46") (pin "1") (pintype "passive"))
      (node (ref "R47") (pin "2") (pintype "passive"))
      (node (ref "V9") (pin "2") (pinfunction "A2_2") (pintype "passive"))
    )
    (net (code "131") (name "Net-(IC8-PC14)") (class "Default")
      (node (ref "C57") (pin "1") (pintype "passive"))
      (node (ref "G2") (pin "1") (pintype "passive"))
      (node (ref "IC8") (pin "8") (pinfunction "PC14_8") (pintype "bidirectional"))
    )
    (net (code "132") (name "Net-(IC8-PC15)") (class "Default")
      (node (ref "C58") (pin "1") (pintype "passive"))
      (node (ref "G2") (pin "2") (pintype "passive"))
      (node (ref "IC8") (pin "9") (pinfunction "PC15_9") (pintype "bidirectional"))
    )
    (net (code "133") (name "Net-(IC8-PD9)") (class "Default")
      (node (ref "IC8") (pin "56") (pinfunction "PD9_56") (pintype "bidirectional"))
      (node (ref "R36") (pin "2") (pintype "passive"))
    )
    (net (code "134") (name "Net-(IC8-PD10)") (class "Default")
      (node (ref "IC8") (pin "57") (pinfunction "PD10_57") (pintype "bidirectional"))
      (node (ref "R37") (pin "2") (pintype "passive"))
    )
    (net (code "135") (name "Net-(IC8-PD11)") (class "Default")
      (node (ref "IC8") (pin "58") (pinfunction "PD11_58") (pintype "bidirectional"))
      (node (ref "R38") (pin "2") (pintype "passive"))
    )
    (net (code "136") (name "Net-(IC8-PE0)") (class "Default")
      (node (ref "IC2") (pin "14") (pinfunction "C_14") (pintype "passive"))
      (node (ref "IC8") (pin "97") (pinfunction "PE0_97") (pintype "bidirectional"))
    )
    (net (code "137") (name "Net-(IC8-PE1)") (class "Default")
      (node (ref "IC2") (pin "16") (pinfunction "C_16") (pintype "passive"))
      (node (ref "IC8") (pin "98") (pinfunction "PE1_98") (pintype "bidirectional"))
    )
    (net (code "138") (name "Net-(IC8-PE2)") (class "Default")
      (node (ref "IC2") (pin "12") (pinfunction "C_12") (pintype "passive"))
      (node (ref "IC8") (pin "1") (pinfunction "PE2_1") (pintype "bidirectional"))
    )
    (net (code "139") (name "Net-(IC8-PE3)") (class "Default")
      (node (ref "IC2") (pin "10") (pinfunction "C_10") (pintype "passive"))
      (node (ref "IC8") (pin "2") (pinfunction "PE3_2") (pintype "bidirectional"))
    )
    (net (code "140") (name "Net-(IC8-Vbat)") (class "Default")
      (node (ref "C37") (pin "1") (pintype "passive"))
      (node (ref "IC8") (pin "6") (pinfunction "Vbat_6") (pintype "power_in"))
      (node (ref "V12") (pin "3") (pinfunction "K_3") (pintype "passive"))
    )
    (net (code "141") (name "Net-(IC8-Vcap_1)") (class "Default")
      (node (ref "C32") (pin "1") (pintype "passive"))
      (node (ref "IC8") (pin "49") (pinfunction "Vcap_1_49") (pintype "power_in"))
    )
    (net (code "142") (name "Net-(IC8-Vcap_2)") (class "Default")
      (node (ref "C33") (pin "1") (pintype "passive"))
      (node (ref "IC8") (pin "73") (pinfunction "Vcap_2_73") (pintype "power_in"))
    )
    (net (code "143") (name "Net-(IC9-IN)") (class "Default")
      (node (ref "C43") (pin "1") (pintype "passive"))
      (node (ref "IC9") (pin "1") (pinfunction "IN_1") (pintype "power_in"))
      (node (ref "L19") (pin "1") (pinfunction "1_1") (pintype "passive"))
    )
    (net (code "144") (name "Net-(IC10-C1+)") (class "Default")
      (node (ref "C5") (pin "1") (pintype "passive"))
      (node (ref "IC10") (pin "1") (pinfunction "C1+_1") (pintype "passive"))
    )
    (net (code "145") (name "Net-(IC10-C1-)") (class "Default")
      (node (ref "C5") (pin "2") (pintype "passive"))
      (node (ref "IC10") (pin "3") (pinfunction "C1-_3") (pintype "passive"))
    )
    (net (code "146") (name "Net-(IC10-C2+)") (class "Default")
      (node (ref "C6") (pin "2") (pintype "passive"))
      (node (ref "IC10") (pin "4") (pinfunction "C2+_4") (pintype "passive"))
    )
    (net (code "147") (name "Net-(IC10-C2-)") (class "Default")
      (node (ref "C6") (pin "1") (pintype "passive"))
      (node (ref "IC10") (pin "5") (pinfunction "C2-_5") (pintype "passive"))
    )
    (net (code "148") (name "Net-(IC10-VS+)") (class "Default")
      (node (ref "C7") (pin "2") (pintype "passive"))
      (node (ref "IC10") (pin "2") (pinfunction "VS+_2") (pintype "power_in"))
    )
    (net (code "149") (name "Net-(IC10-VS-)") (class "Default")
      (node (ref "C8") (pin "2") (pintype "passive"))
      (node (ref "IC10") (pin "6") (pinfunction "VS-_6") (pintype "power_in"))
    )
    (net (code "150") (name "Net-(IC11-IN)") (class "Default")
      (node (ref "C12") (pin "1") (pintype "passive"))
      (node (ref "IC11") (pin "3") (pinfunction "~{SD}_3") (pintype "passive"))
      (node (ref "IC11") (pin "5") (pinfunction "IN_5") (pintype "input"))
      (node (ref "R64") (pin "1") (pintype "passive"))
    )
    (net (code "151") (name "Net-(IC11-NR)") (class "Default")
      (node (ref "C13") (pin "2") (pintype "passive"))
      (node (ref "IC11") (pin "2") (pinfunction "NR_2") (pintype "power_in"))
    )
    (net (code "152") (name "Net-(JMP2-Pad2)") (class "Default")
      (node (ref "JMP2") (pin "2") (pintype "passive"))
      (node (ref "X20") (pin "2") (pinfunction "2_2") (pintype "passive"))
      (node (ref "X5") (pin "2") (pinfunction "2_2") (pintype "passive"))
    )
    (net (code "153") (name "Net-(L1-Pad2)") (class "Default")
      (node (ref "L1") (pin "2") (pinfunction "2_2") (pintype "passive"))
      (node (ref "X15") (pin "10") (pinfunction "10_10") (pintype "passive"))
    )
    (net (code "154") (name "Net-(L2-Pad2)") (class "Default")
      (node (ref "L2") (pin "2") (pinfunction "2_2") (pintype "passive"))
      (node (ref "X16") (pin "2") (pinfunction "2_2") (pintype "passive"))
    )
    (net (code "155") (name "Net-(L4-Pad2)") (class "Default")
      (node (ref "L4") (pin "2") (pinfunction "2_2") (pintype "passive"))
      (node (ref "X11") (pin "1") (pinfunction "1_1") (pintype "passive"))
    )
    (net (code "156") (name "Net-(L5-Pad2)") (class "Default")
      (node (ref "L5") (pin "2") (pinfunction "2_2") (pintype "passive"))
      (node (ref "X11") (pin "3") (pinfunction "3_3") (pintype "passive"))
    )
    (net (code "157") (name "Net-(L6-Pad2)") (class "Default")
      (node (ref "L6") (pin "2") (pinfunction "2_2") (pintype "passive"))
      (node (ref "X11") (pin "5") (pinfunction "5_5") (pintype "passive"))
    )
    (net (code "158") (name "Net-(L7-Pad2)") (class "Default")
      (node (ref "L7") (pin "2") (pinfunction "2_2") (pintype "passive"))
      (node (ref "X11") (pin "7") (pinfunction "7_7") (pintype "passive"))
    )
    (net (code "159") (name "Net-(L8-Pad2)") (class "Default")
      (node (ref "L8") (pin "2") (pinfunction "2_2") (pintype "passive"))
      (node (ref "X12") (pin "5") (pinfunction "5_5") (pintype "passive"))
    )
    (net (code "160") (name "Net-(L9-Pad2)") (class "Default")
      (node (ref "L9") (pin "2") (pinfunction "2_2") (pintype "passive"))
      (node (ref "X12") (pin "3") (pinfunction "3_3") (pintype "passive"))
    )
    (net (code "161") (name "Net-(L10-Pad2)") (class "Default")
      (node (ref "L10") (pin "2") (pinfunction "2_2") (pintype "passive"))
      (node (ref "X12") (pin "1") (pinfunction "1_1") (pintype "passive"))
    )
    (net (code "162") (name "Net-(L11-Pad2)") (class "Default")
      (node (ref "L11") (pin "2") (pinfunction "2_2") (pintype "passive"))
      (node (ref "X18") (pin "2") (pinfunction "2_2") (pintype "passive"))
    )
    (net (code "163") (name "Net-(L12-Pad2)") (class "Default")
      (node (ref "L12") (pin "2") (pinfunction "2_2") (pintype "passive"))
      (node (ref "X14") (pin "2") (pinfunction "2_2") (pintype "passive"))
    )
    (net (code "164") (name "Net-(L13-Pad2)") (class "Default")
      (node (ref "L13") (pin "2") (pinfunction "2_2") (pintype "passive"))
      (node (ref "X16") (pin "5") (pinfunction "5_5") (pintype "passive"))
    )
    (net (code "165") (name "Net-(L14-Pad2)") (class "Default")
      (node (ref "L14") (pin "2") (pinfunction "2_2") (pintype "passive"))
      (node (ref "X16") (pin "8") (pinfunction "8_8") (pintype "passive"))
    )
    (net (code "166") (name "Net-(L15-Pad2)") (class "Default")
      (node (ref "L15") (pin "2") (pinfunction "2_2") (pintype "passive"))
      (node (ref "X16") (pin "9") (pinfunction "9_9") (pintype "passive"))
    )
    (net (code "167") (name "Net-(L16-Pad2)") (class "Default")
      (node (ref "L16") (pin "2") (pinfunction "2_2") (pintype "passive"))
      (node (ref "X14") (pin "1") (pinfunction "1_1") (pintype "passive"))
    )
    (net (code "168") (name "Net-(L17-Pad2)") (class "Default")
      (node (ref "L17") (pin "2") (pinfunction "2_2") (pintype "passive"))
      (node (ref "X20") (pin "3") (pinfunction "3_3") (pintype "passive"))
    )
    (net (code "169") (name "Net-(L20-Pad2)") (class "Default")
      (node (ref "L20") (pin "2") (pinfunction "2_2") (pintype "passive"))
      (node (ref "X5") (pin "3") (pinfunction "3_3") (pintype "passive"))
    )
    (net (code "170") (name "Net-(L21-Pad2)") (class "Default")
      (node (ref "L21") (pin "2") (pinfunction "2_2") (pintype "passive"))
      (node (ref "X15") (pin "9") (pinfunction "9_9") (pintype "passive"))
    )
    (net (code "171") (name "Net-(L22-Pad2)") (class "Default")
      (node (ref "L22") (pin "2") (pinfunction "2_2") (pintype "passive"))
      (node (ref "X20") (pin "4") (pinfunction "4_4") (pintype "passive"))
      (node (ref "X5") (pin "4") (pinfunction "4_4") (pintype "passive"))
    )
    (net (code "172") (name "Net-(R5-Pad2)") (class "Default")
      (node (ref "R5") (pin "2") (pintype "passive"))
      (node (ref "V2") (pin "B") (pintype "passive"))
    )
    (net (code "173") (name "Net-(R7-Pad1)") (class "Default")
      (node (ref "R7") (pin "1") (pintype "passive"))
      (node (ref "V5") (pin "K") (pintype "passive"))
    )
    (net (code "174") (name "Net-(R8-Pad1)") (class "Default")
      (node (ref "R8") (pin "1") (pintype "passive"))
      (node (ref "X15") (pin "6") (pinfunction "6_6") (pintype "passive"))
    )
    (net (code "175") (name "Net-(R10-Pad1)") (class "Default")
      (node (ref "R10") (pin "1") (pintype "passive"))
      (node (ref "X15") (pin "4") (pinfunction "4_4") (pintype "passive"))
    )
    (net (code "176") (name "Net-(R11-Pad1)") (class "Default")
      (node (ref "R11") (pin "1") (pintype "passive"))
      (node (ref "X15") (pin "3") (pinfunction "3_3") (pintype "passive"))
    )
    (net (code "177") (name "Net-(R14-Pad1)") (class "Default")
      (node (ref "R14") (pin "1") (pintype "passive"))
      (node (ref "V6") (pin "B") (pinfunction "B_B") (pintype "passive"))
    )
    (net (code "178") (name "Net-(R20-Pad2)") (class "Default")
      (node (ref "R20") (pin "2") (pintype "passive"))
      (node (ref "V7") (pin "1") (pinfunction "1_1") (pintype "passive"))
      (node (ref "X9") (pin "2") (pinfunction "2_2") (pintype "passive"))
    )
    (net (code "179") (name "Net-(R21-Pad2)") (class "Default")
      (node (ref "R21") (pin "2") (pintype "passive"))
      (node (ref "V7") (pin "5") (pinfunction "5_5") (pintype "passive"))
      (node (ref "X9") (pin "3") (pinfunction "3_3") (pintype "passive"))
    )
    (net (code "180") (name "Net-(R35-Pad1)") (class "Default")
      (node (ref "R35") (pin "1") (pintype "passive"))
      (node (ref "X10") (pin "3") (pinfunction "3_3") (pintype "passive"))
    )
    (net (code "181") (name "Net-(R35-Pad2)") (class "Default")
      (node (ref "R35") (pin "2") (pintype "passive"))
      (node (ref "V8") (pin "B") (pintype "passive"))
    )
    (net (code "182") (name "Net-(V15-A1)") (class "Default")
      (node (ref "JP1") (pin "1") (pintype "passive"))
      (node (ref "L3") (pin "2") (pinfunction "2_2") (pintype "passive"))
      (node (ref "V15") (pin "1") (pinfunction "A1_1") (pintype "passive"))
    )
    (net (code "183") (name "Pgnd") (class "Default")
      (node (ref "A1") (pin "3") (pinfunction "GND_3") (pintype "passive"))
      (node (ref "A2") (pin "3") (pinfunction "GND_3") (pintype "passive"))
      (node (ref "C1") (pin "2") (pintype "passive"))
      (node (ref "C2") (pin "1") (pintype "passive"))
      (node (ref "C25") (pin "2") (pintype "passive"))
      (node (ref "C29") (pin "2") (pintype "passive"))
      (node (ref "H12") (pin "K") (pintype "passive"))
      (node (ref "IC7") (pin "9") (pinfunction "GND_9") (pintype "passive"))
      (node (ref "JMP1") (pin "1") (pinfunction "1_1") (pintype "passive"))
      (node (ref "R1") (pin "2") (pintype "passive"))
      (node (ref "R39") (pin "1") (pintype "passive"))
      (node (ref "R40") (pin "1") (pintype "passive"))
      (node (ref "R63") (pin "2") (pintype "passive"))
      (node (ref "V1") (pin "2") (pinfunction "2_2") (pintype "passive"))
      (node (ref "V2") (pin "E") (pintype "passive"))
      (node (ref "V8") (pin "E") (pintype "passive"))
      (node (ref "X1") (pin "2") (pinfunction "2_2") (pintype "passive"))
      (node (ref "X1") (pin "4") (pinfunction "4_4") (pintype "passive"))
      (node (ref "X15") (pin "2") (pinfunction "2_2") (pintype "passive"))
      (node (ref "X2") (pin "2") (pinfunction "2_2") (pintype "passive"))
      (node (ref "X20") (pin "1") (pinfunction "1_1") (pintype "passive"))
      (node (ref "X5") (pin "1") (pinfunction "1_1") (pintype "passive"))
    )
    (net (code "184") (name "Shield") (class "Default")
      (node (ref "JMP1") (pin "3") (pinfunction "3_3") (pintype "passive"))
      (node (ref "X16") (pin "10") (pinfunction "10_10") (pintype "passive"))
      (node (ref "X6") (pin "7") (pinfunction "7_7") (pintype "passive"))
      (node (ref "X7") (pin "7") (pinfunction "7_7") (pintype "passive"))
    )
    (net (code "185") (name "VCCIO") (class "Default")
      (node (ref "C23") (pin "2") (pintype "passive"))
      (node (ref "H10") (pin "A") (pinfunction "A_A") (pintype "passive"))
      (node (ref "H11") (pin "A") (pinfunction "A_A") (pintype "passive"))
      (node (ref "H9") (pin "A") (pinfunction "A_A") (pintype "passive"))
      (node (ref "IC5") (pin "17") (pinfunction "3V3OUT_17") (pintype "passive"))
      (node (ref "IC5") (pin "4") (pinfunction "VCCIO_4") (pintype "passive"))
    )
    (net (code "186") (name "Vref_3V3") (class "Default")
      (node (ref "C41") (pin "1") (pintype "passive"))
      (node (ref "C42") (pin "1") (pintype "passive"))
      (node (ref "IC8") (pin "21") (pinfunction "Vref+_21") (pintype "power_in"))
      (node (ref "IC8") (pin "22") (pinfunction "VddA_22") (pintype "power_in"))
      (node (ref "IC9") (pin "2") (pinfunction "OUT_2") (pintype "power_in"))
      (node (ref "R53") (pin "2") (pintype "passive"))
      (node (ref "R54") (pin "2") (pintype "passive"))
    )
    (net (code "187") (name "unconnected-(A2-ON{slash}OFF-Pad1)") (class "Default")
      (node (ref "A2") (pin "1") (pinfunction "ON/OFF_1") (pintype "passive"))
    )
    (net (code "188") (name "unconnected-(A2-TRIM-Pad4)") (class "Default")
      (node (ref "A2") (pin "4") (pinfunction "TRIM_4") (pintype "passive"))
    )
    (net (code "189") (name "unconnected-(B1-NC-Pad1)") (class "Default")
      (node (ref "B1") (pin "1") (pinfunction "NC_1") (pintype "passive"))
    )
    (net (code "190") (name "unconnected-(B1-NC-Pad5)") (class "Default")
      (node (ref "B1") (pin "5") (pinfunction "NC_5") (pintype "passive"))
    )
    (net (code "191") (name "unconnected-(B1-NC-Pad6)") (class "Default")
      (node (ref "B1") (pin "6") (pinfunction "NC_6") (pintype "passive"))
    )
    (net (code "192") (name "unconnected-(B1-NC-Pad7)") (class "Default")
      (node (ref "B1") (pin "7") (pinfunction "NC_7") (pintype "passive"))
    )
    (net (code "193") (name "unconnected-(B1-NC-Pad8)") (class "Default")
      (node (ref "B1") (pin "8") (pinfunction "NC_8") (pintype "passive"))
    )
    (net (code "194") (name "unconnected-(B2-NC-Pad1)") (class "Default")
      (node (ref "B2") (pin "1") (pinfunction "NC_1") (pintype "passive"))
    )
    (net (code "195") (name "unconnected-(B2-NC-Pad5)") (class "Default")
      (node (ref "B2") (pin "5") (pinfunction "NC_5") (pintype "passive"))
    )
    (net (code "196") (name "unconnected-(B2-NC-Pad6)") (class "Default")
      (node (ref "B2") (pin "6") (pinfunction "NC_6") (pintype "passive"))
    )
    (net (code "197") (name "unconnected-(B2-NC-Pad7)") (class "Default")
      (node (ref "B2") (pin "7") (pinfunction "NC_7") (pintype "passive"))
    )
    (net (code "198") (name "unconnected-(B2-NC-Pad8)") (class "Default")
      (node (ref "B2") (pin "8") (pinfunction "NC_8") (pintype "passive"))
    )
    (net (code "199") (name "unconnected-(B3-NC-Pad1)") (class "Default")
      (node (ref "B3") (pin "1") (pinfunction "NC_1") (pintype "passive"))
    )
    (net (code "200") (name "unconnected-(B3-NC-Pad5)") (class "Default")
      (node (ref "B3") (pin "5") (pinfunction "NC_5") (pintype "passive"))
    )
    (net (code "201") (name "unconnected-(B3-NC-Pad6)") (class "Default")
      (node (ref "B3") (pin "6") (pinfunction "NC_6") (pintype "passive"))
    )
    (net (code "202") (name "unconnected-(B3-NC-Pad7)") (class "Default")
      (node (ref "B3") (pin "7") (pinfunction "NC_7") (pintype "passive"))
    )
    (net (code "203") (name "unconnected-(B3-NC-Pad8)") (class "Default")
      (node (ref "B3") (pin "8") (pinfunction "NC_8") (pintype "passive"))
    )
    (net (code "204") (name "unconnected-(B4-NC-Pad1)") (class "Default")
      (node (ref "B4") (pin "1") (pinfunction "NC_1") (pintype "passive"))
    )
    (net (code "205") (name "unconnected-(B4-NC-Pad5)") (class "Default")
      (node (ref "B4") (pin "5") (pinfunction "NC_5") (pintype "passive"))
    )
    (net (code "206") (name "unconnected-(B4-NC-Pad6)") (class "Default")
      (node (ref "B4") (pin "6") (pinfunction "NC_6") (pintype "passive"))
    )
    (net (code "207") (name "unconnected-(B4-NC-Pad7)") (class "Default")
      (node (ref "B4") (pin "7") (pinfunction "NC_7") (pintype "passive"))
    )
    (net (code "208") (name "unconnected-(B4-NC-Pad8)") (class "Default")
      (node (ref "B4") (pin "8") (pinfunction "NC_8") (pintype "passive"))
    )
    (net (code "209") (name "unconnected-(IC5-NC-Pad8)") (class "Default")
      (node (ref "IC5") (pin "8") (pinfunction "NC_8") (pintype "passive"))
    )
    (net (code "210") (name "unconnected-(IC5-NC-Pad24)") (class "Default")
      (node (ref "IC5") (pin "24") (pinfunction "NC_24") (pintype "passive"))
    )
    (net (code "211") (name "unconnected-(IC5-OSCI-Pad27)") (class "Default")
      (node (ref "IC5") (pin "27") (pinfunction "OSCI_27") (pintype "passive"))
    )
    (net (code "212") (name "unconnected-(IC5-OSCO-Pad28)") (class "Default")
      (node (ref "IC5") (pin "28") (pinfunction "OSCO_28") (pintype "passive"))
    )
    (net (code "213") (name "unconnected-(IC5-~{CTS}-Pad11)") (class "Default")
      (node (ref "IC5") (pin "11") (pinfunction "~{CTS}_11") (pintype "passive"))
    )
    (net (code "214") (name "unconnected-(IC5-~{DCD}-Pad10)") (class "Default")
      (node (ref "IC5") (pin "10") (pinfunction "~{DCD}_10") (pintype "passive"))
    )
    (net (code "215") (name "unconnected-(IC5-~{DSR}-Pad9)") (class "Default")
      (node (ref "IC5") (pin "9") (pinfunction "~{DSR}_9") (pintype "passive"))
    )
    (net (code "216") (name "unconnected-(IC5-~{DTR}-Pad2)") (class "Default")
      (node (ref "IC5") (pin "2") (pinfunction "~{DTR}_2") (pintype "passive"))
    )
    (net (code "217") (name "unconnected-(IC5-~{RI}-Pad6)") (class "Default")
      (node (ref "IC5") (pin "6") (pinfunction "~{RI}_6") (pintype "passive"))
    )
    (net (code "218") (name "unconnected-(IC5-~{RTS}-Pad3)") (class "Default")
      (node (ref "IC5") (pin "3") (pinfunction "~{RTS}_3") (pintype "passive"))
    )
    (net (code "219") (name "unconnected-(IC6B-VCC-Pad8)") (class "Default")
      (node (ref "IC6") (pin "8") (pinfunction "VCC_8") (pintype "power_in"))
    )
    (net (code "220") (name "unconnected-(IC6B-VEE-Pad4)") (class "Default")
      (node (ref "IC6") (pin "4") (pinfunction "VEE_4") (pintype "power_in"))
    )
    (net (code "221") (name "unconnected-(IC8-PA5{slash}DAC_OUT2{slash}ADC12_IN5-Pad30)") (class "Default")
      (node (ref "IC8") (pin "30") (pinfunction "PA5/DAC_OUT2/ADC12_IN5_30") (pintype "bidirectional"))
    )
    (net (code "222") (name "unconnected-(IC8-PA7{slash}ADC12_IN7{slash}TIM3_CH2-Pad32)") (class "Default")
      (node (ref "IC8") (pin "32") (pinfunction "PA7/ADC12_IN7/TIM3_CH2_32") (pintype "bidirectional"))
    )
    (net (code "223") (name "unconnected-(IC8-PA8-Pad67)") (class "Default")
      (node (ref "IC8") (pin "67") (pinfunction "PA8_67") (pintype "bidirectional"))
    )
    (net (code "224") (name "unconnected-(IC8-PA11{slash}USBDM-Pad70)") (class "Default")
      (node (ref "IC8") (pin "70") (pinfunction "PA11/USBDM_70") (pintype "bidirectional"))
    )
    (net (code "225") (name "unconnected-(IC8-PA12{slash}USBDP-Pad71)") (class "Default")
      (node (ref "IC8") (pin "71") (pinfunction "PA12/USBDP_71") (pintype "bidirectional"))
    )
    (net (code "226") (name "unconnected-(IC8-PA15{slash}TIM2_CH1-Pad77)") (class "Default")
      (node (ref "IC8") (pin "77") (pinfunction "PA15/TIM2_CH1_77") (pintype "bidirectional"))
    )
    (net (code "227") (name "unconnected-(IC8-PB7{slash}{slash}I2C1_SDA-Pad93)") (class "Default")
      (node (ref "IC8") (pin "93") (pinfunction "PB7//I2C1_SDA_93") (pintype "bidirectional"))
    )
    (net (code "228") (name "unconnected-(IC8-PB9{slash}TIM11_CH1-Pad96)") (class "Default")
      (node (ref "IC8") (pin "96") (pinfunction "PB9/TIM11_CH1_96") (pintype "bidirectional"))
    )
    (net (code "229") (name "unconnected-(IC8-PB10{slash}TIM2_CH3-Pad47)") (class "Default")
      (node (ref "IC8") (pin "47") (pinfunction "PB10/TIM2_CH3_47") (pintype "bidirectional"))
    )
    (net (code "230") (name "unconnected-(IC8-PB11{slash}TIM2_CH4{slash}USART3_RX-Pad48)") (class "Default")
      (node (ref "IC8") (pin "48") (pinfunction "PB11/TIM2_CH4/USART3_RX_48") (pintype "bidirectional"))
    )
    (net (code "231") (name "unconnected-(IC8-PB12-Pad51)") (class "Default")
      (node (ref "IC8") (pin "51") (pinfunction "PB12_51") (pintype "bidirectional"))
    )
    (net (code "232") (name "unconnected-(IC8-PC12-Pad80)") (class "Default")
      (node (ref "IC8") (pin "80") (pinfunction "PC12_80") (pintype "bidirectional"))
    )
    (net (code "233") (name "unconnected-(IC8-PC13-Pad7)") (class "Default")
      (node (ref "IC8") (pin "7") (pinfunction "PC13_7") (pintype "bidirectional"))
    )
    (net (code "234") (name "unconnected-(IC8-PD8-Pad55)") (class "Default")
      (node (ref "IC8") (pin "55") (pinfunction "PD8_55") (pintype "bidirectional"))
    )
    (net (code "235") (name "unconnected-(IC8-PD14{slash}TIM4_CH3-Pad61)") (class "Default")
      (node (ref "IC8") (pin "61") (pinfunction "PD14/TIM4_CH3_61") (pintype "bidirectional"))
    )
    (net (code "236") (name "unconnected-(IC8-PD15{slash}TIM4_CH4-Pad62)") (class "Default")
      (node (ref "IC8") (pin "62") (pinfunction "PD15/TIM4_CH4_62") (pintype "bidirectional"))
    )
    (net (code "237") (name "unconnected-(IC8-PE4-Pad3)") (class "Default")
      (node (ref "IC8") (pin "3") (pinfunction "PE4_3") (pintype "bidirectional"))
    )
    (net (code "238") (name "unconnected-(IC8-PE7-Pad38)") (class "Default")
      (node (ref "IC8") (pin "38") (pinfunction "PE7_38") (pintype "bidirectional"))
    )
    (net (code "239") (name "unconnected-(IC8-PE8-Pad39)") (class "Default")
      (node (ref "IC8") (pin "39") (pinfunction "PE8_39") (pintype "bidirectional"))
    )
    (net (code "240") (name "unconnected-(IC8-PE10-Pad41)") (class "Default")
      (node (ref "IC8") (pin "41") (pinfunction "PE10_41") (pintype "bidirectional"))
    )
    (net (code "241") (name "unconnected-(IC8-PE12-Pad43)") (class "Default")
      (node (ref "IC8") (pin "43") (pinfunction "PE12_43") (pintype "bidirectional"))
    )
    (net (code "242") (name "unconnected-(IC8-PE15-Pad46)") (class "Default")
      (node (ref "IC8") (pin "46") (pinfunction "PE15_46") (pintype "bidirectional"))
    )
    (net (code "243") (name "unconnected-(IC10-DIN2-Pad10)") (class "Default")
      (node (ref "IC10") (pin "10") (pinfunction "DIN2_10") (pintype "input"))
    )
    (net (code "244") (name "unconnected-(IC10-RIN2-Pad8)") (class "Default")
      (node (ref "IC10") (pin "8") (pinfunction "RIN2_8") (pintype "input"))
    )
    (net (code "245") (name "unconnected-(IC10-~{DOUT2}-Pad7)") (class "Default")
      (node (ref "IC10") (pin "7") (pinfunction "~{DOUT2}_7") (pintype "output"))
    )
    (net (code "246") (name "unconnected-(IC10-~{ROUT2}-Pad9)") (class "Default")
      (node (ref "IC10") (pin "9") (pinfunction "~{ROUT2}_9") (pintype "output"))
    )
    (net (code "247") (name "unconnected-(IC11-~{ERR}-Pad6)") (class "Default")
      (node (ref "IC11") (pin "6") (pinfunction "~{ERR}_6") (pintype "power_in"))
    )
    (net (code "248") (name "unconnected-(V1-Pad3)") (class "Default")
      (node (ref "V1") (pin "3") (pinfunction "3_3") (pintype "passive"))
    )
    (net (code "249") (name "unconnected-(V7-Pad3)") (class "Default")
      (node (ref "V7") (pin "3") (pinfunction "3_3") (pintype "passive"))
    )
    (net (code "250") (name "unconnected-(X8-Pad2)") (class "Default")
      (node (ref "X8") (pin "2") (pinfunction "2_2") (pintype "passive"))
    )
    (net (code "251") (name "unconnected-(X9-Pad4)") (class "Default")
      (node (ref "X9") (pin "4") (pinfunction "4_4") (pintype "passive"))
    )
    (net (code "252") (name "unconnected-(X10-Pad2)") (class "Default")
      (node (ref "X10") (pin "2") (pinfunction "2_2") (pintype "passive"))
    )
  )
)
